# Dashboard_rev6.net
KiCad netlist of a schematic drawn in EAGLE
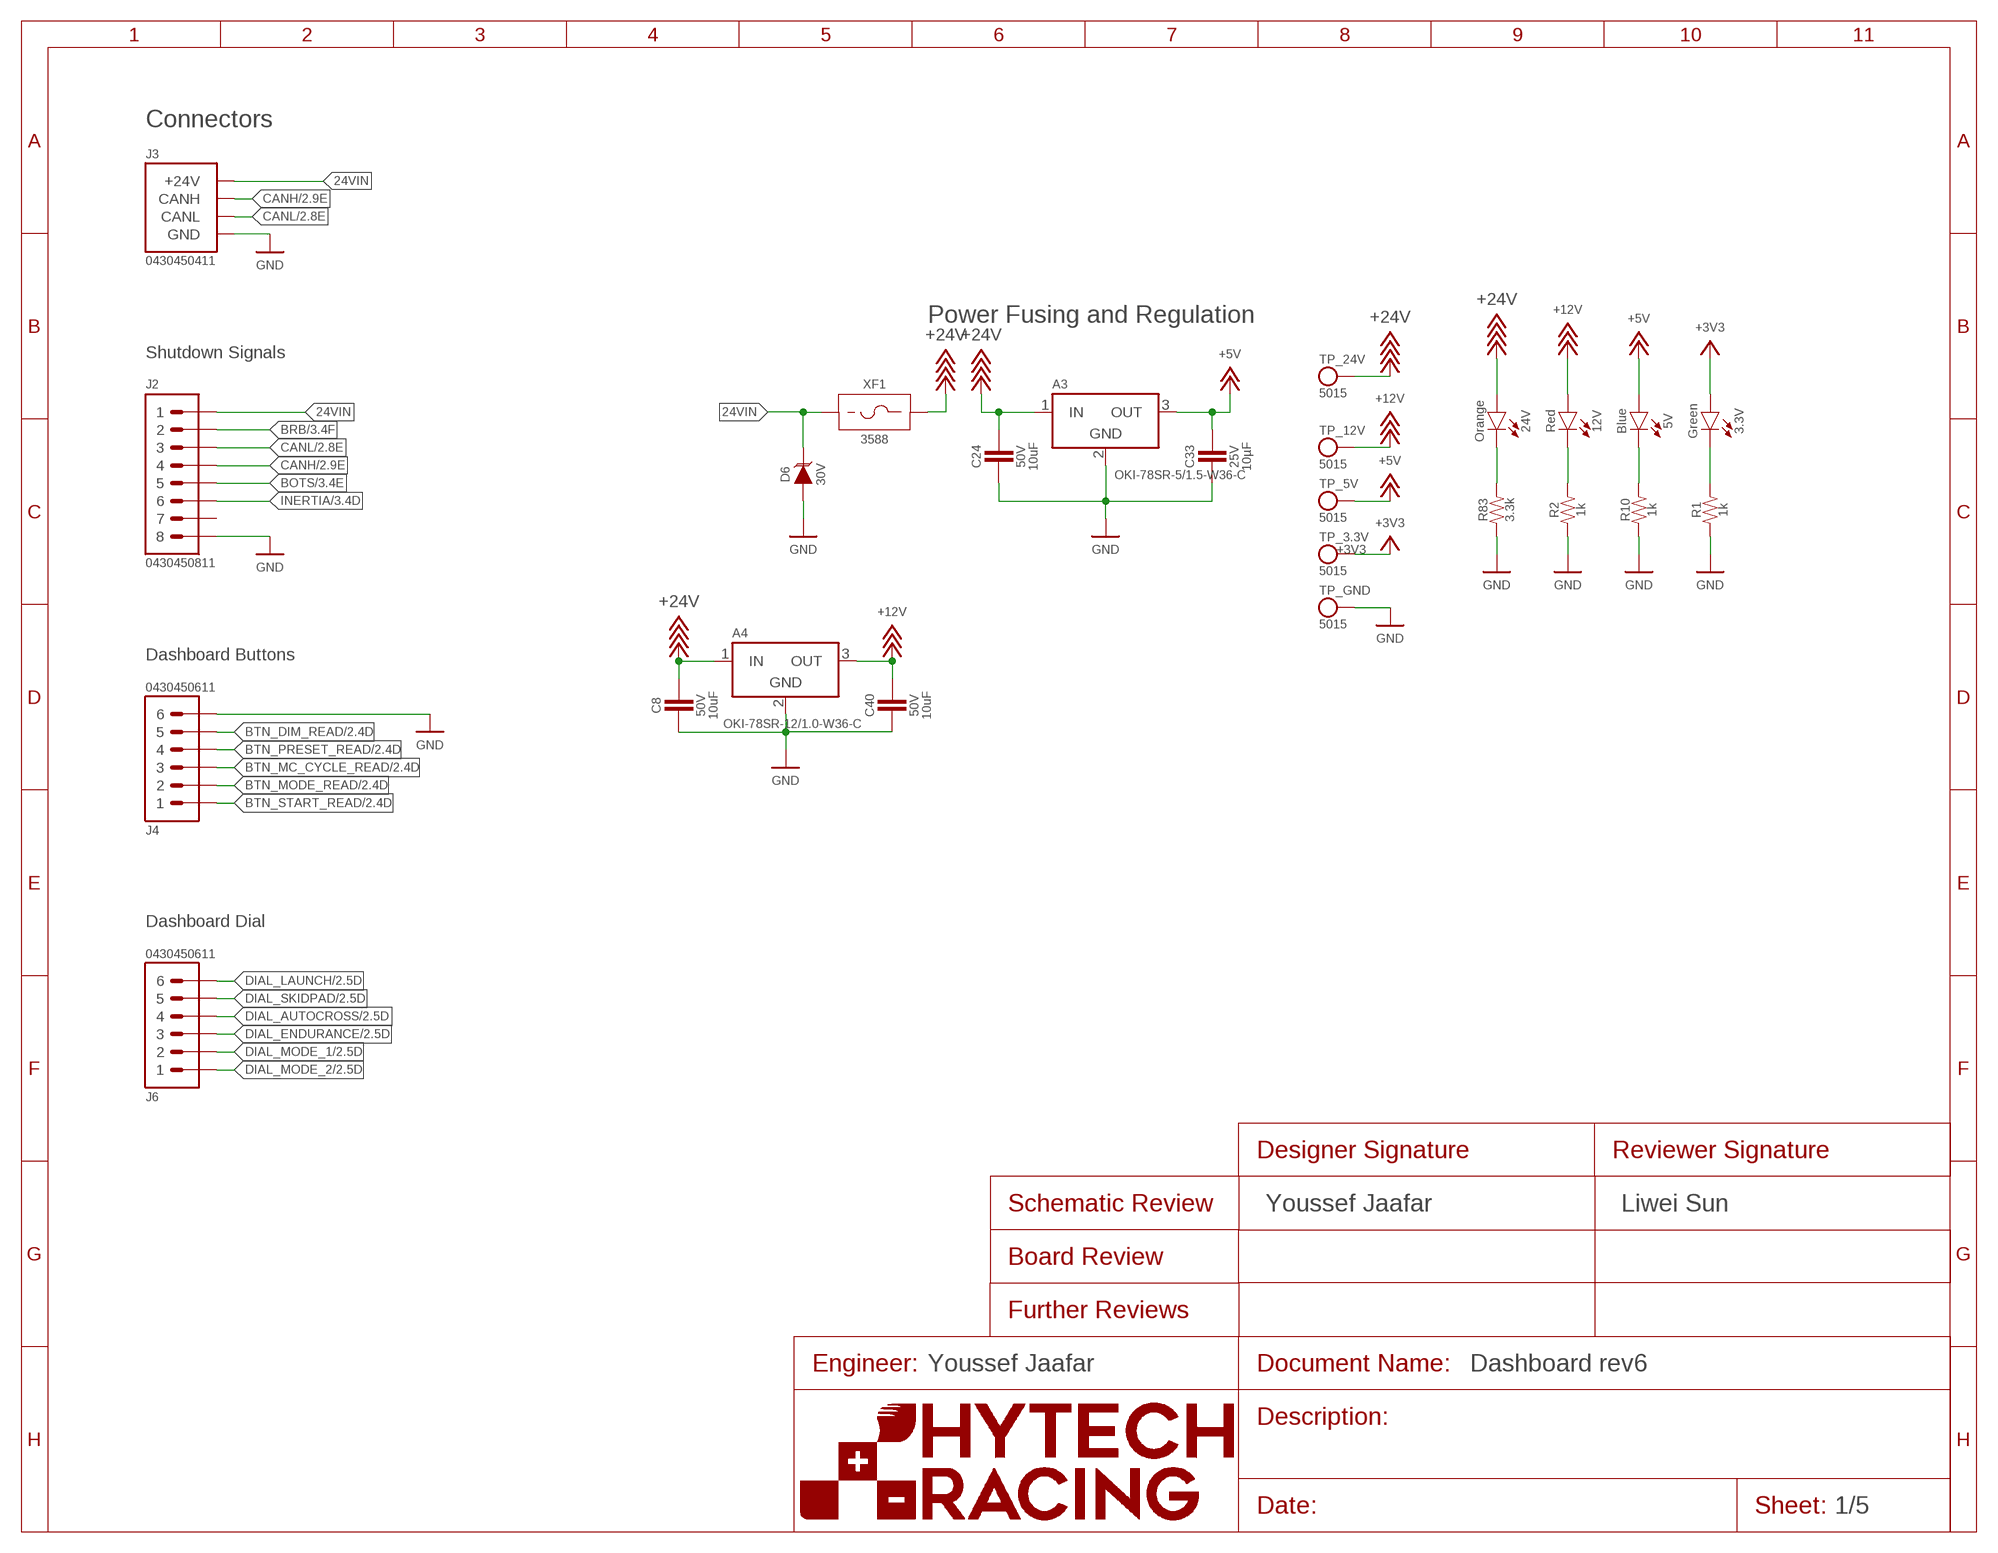
[diagram p0: schematic, sheet 1]
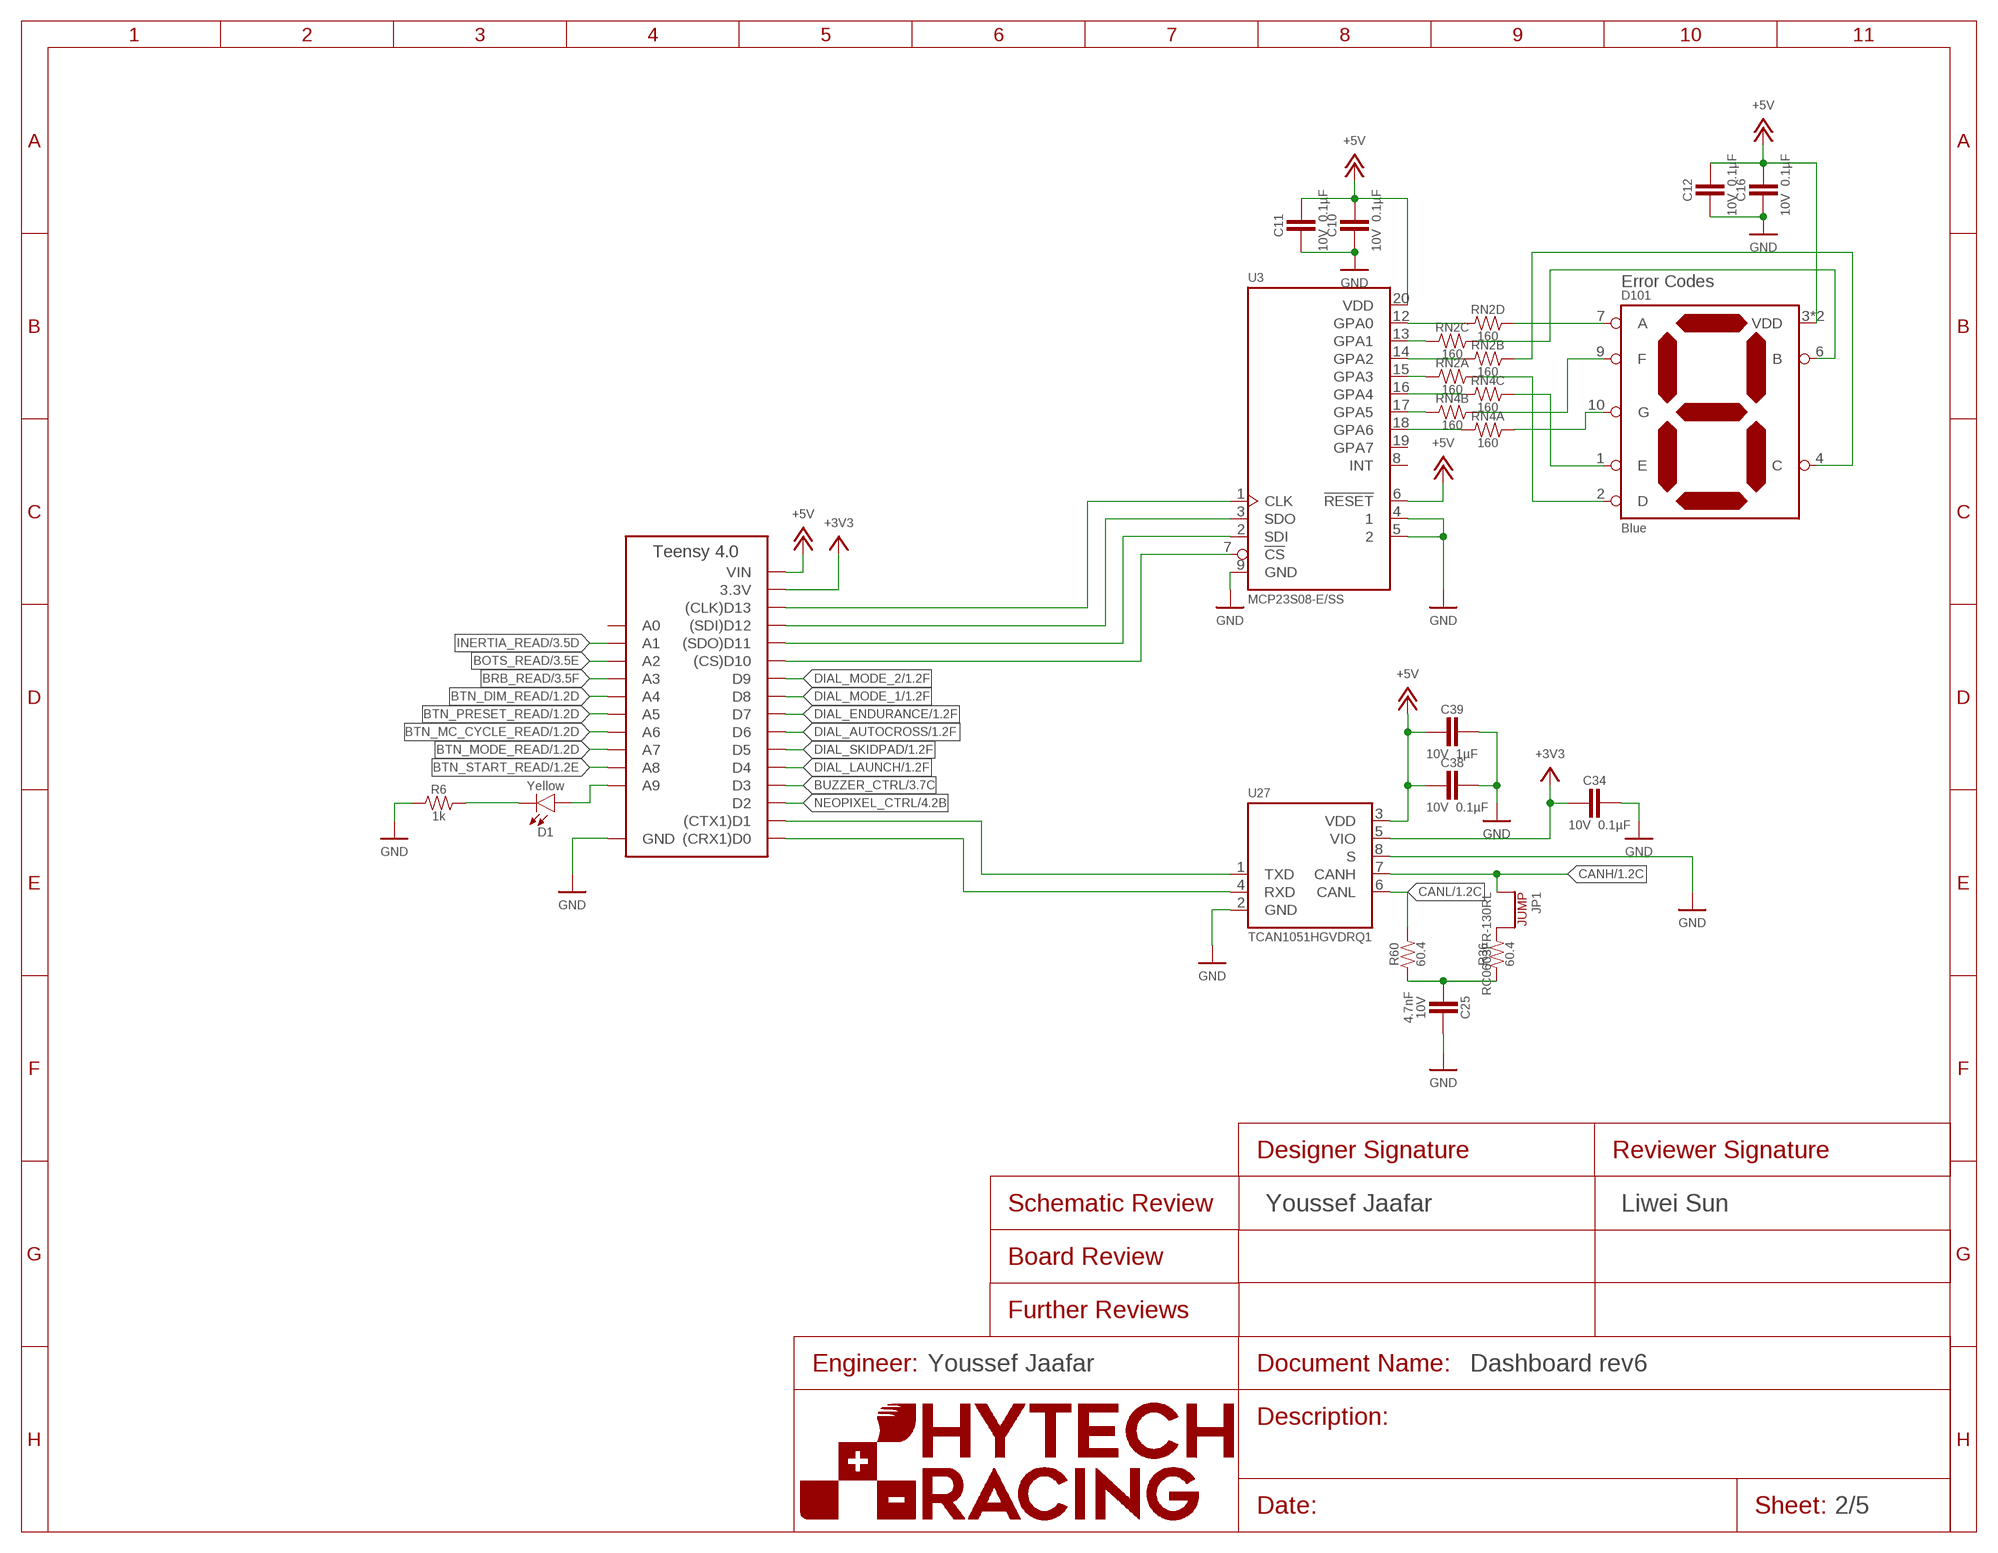
[diagram p1: schematic, sheet 2]
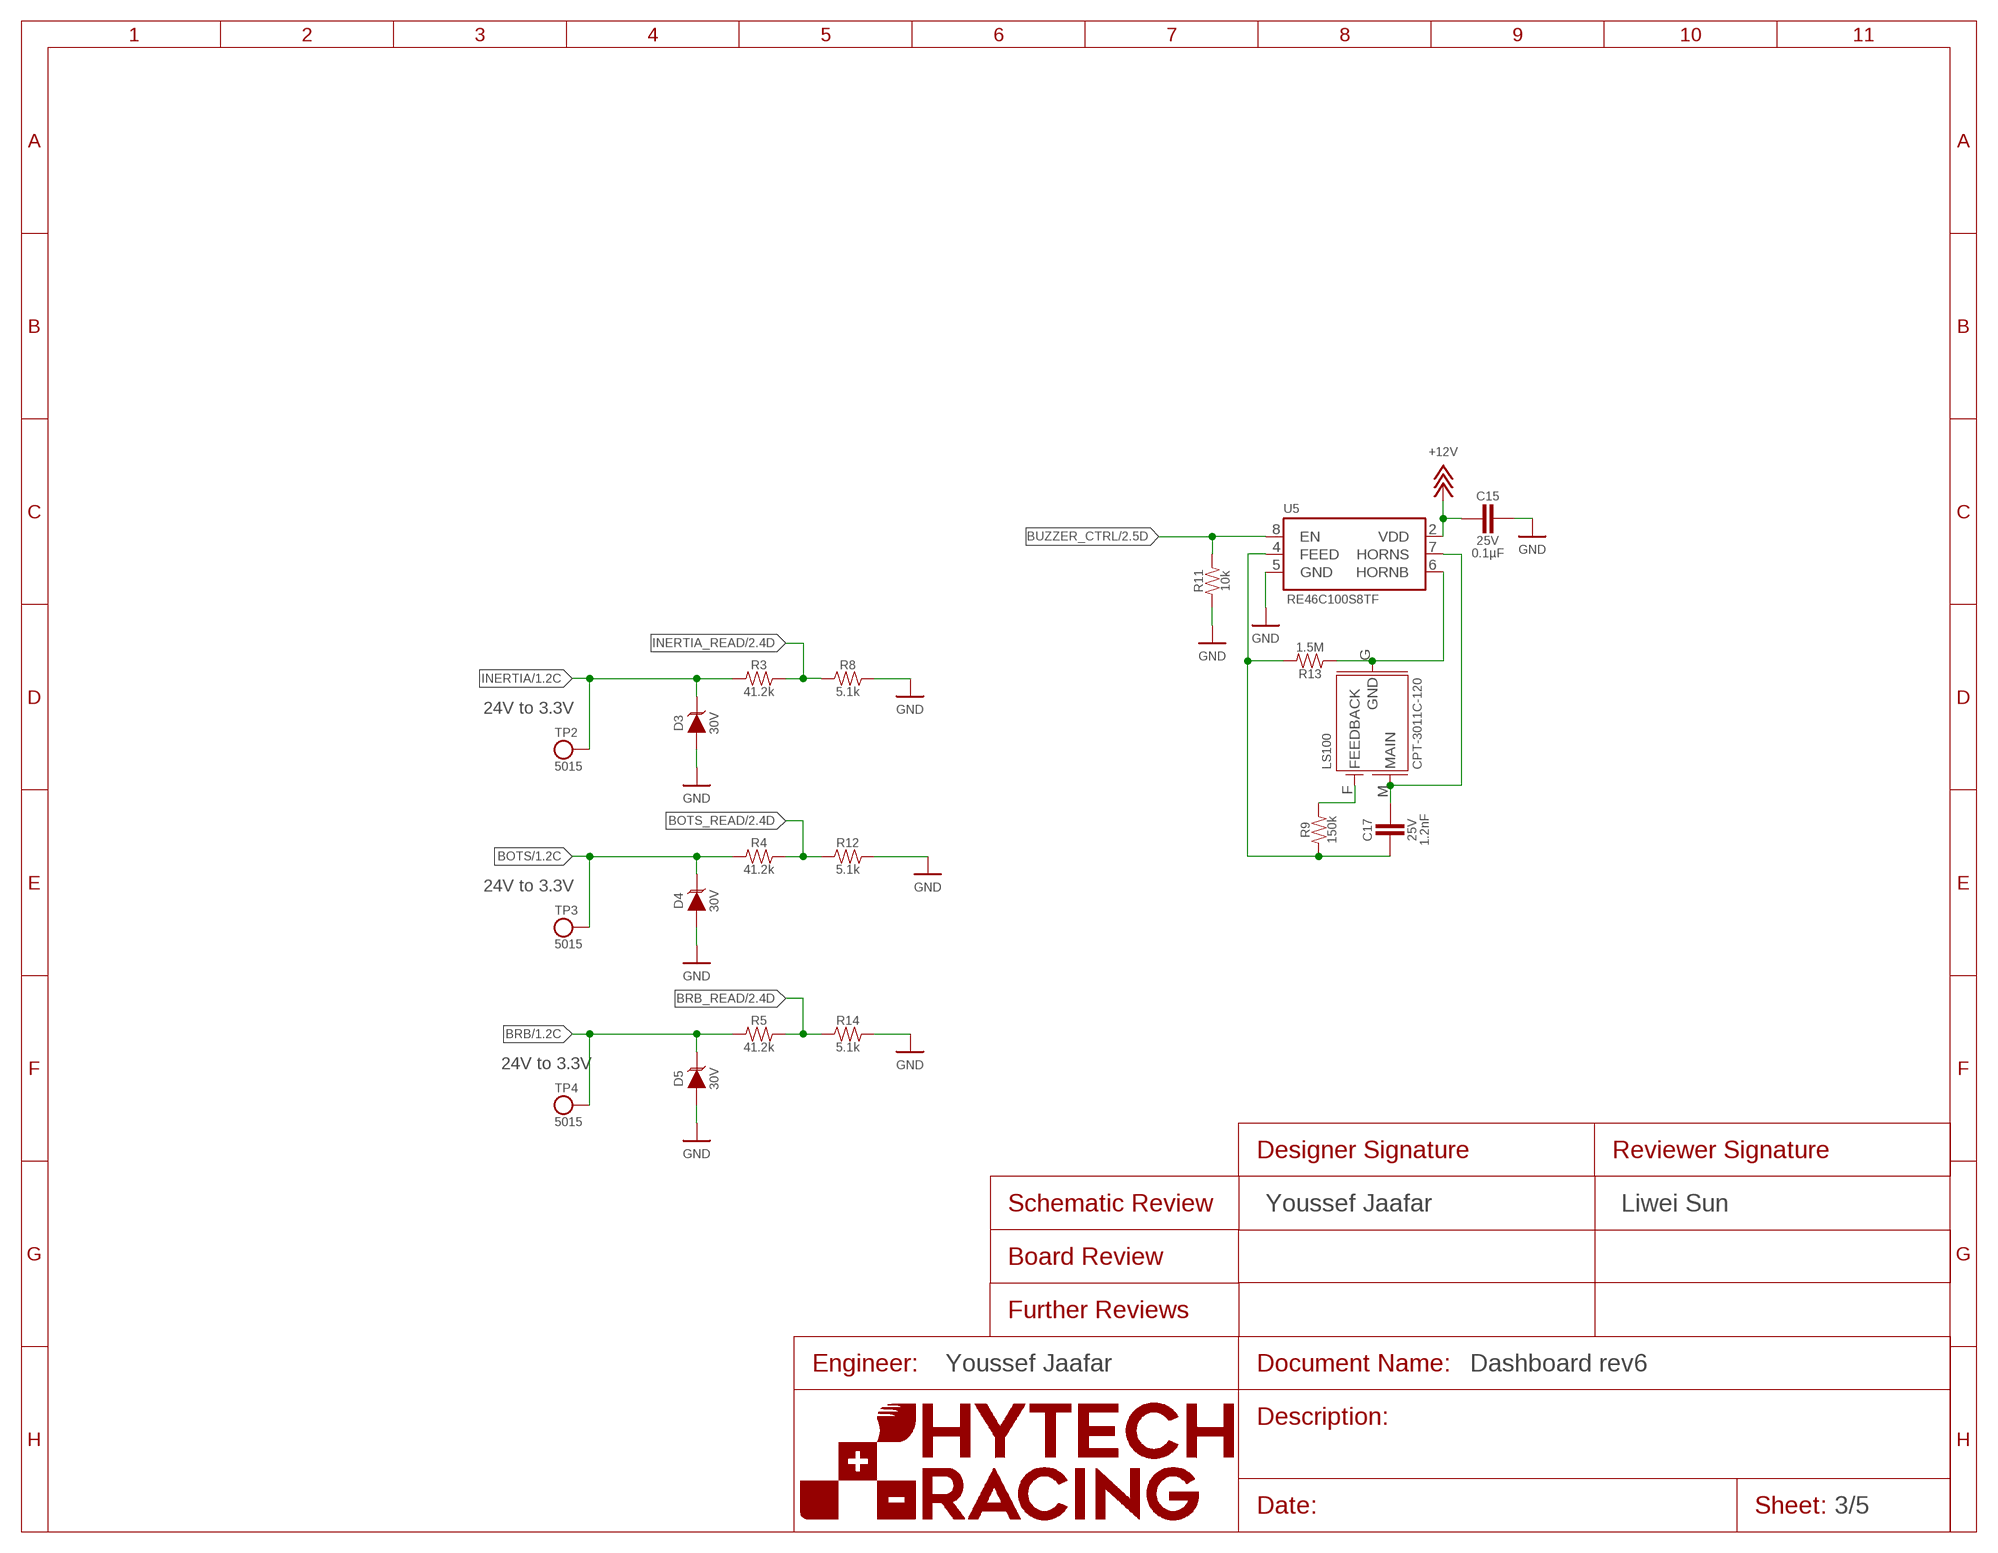
[diagram p2: schematic, sheet 3]
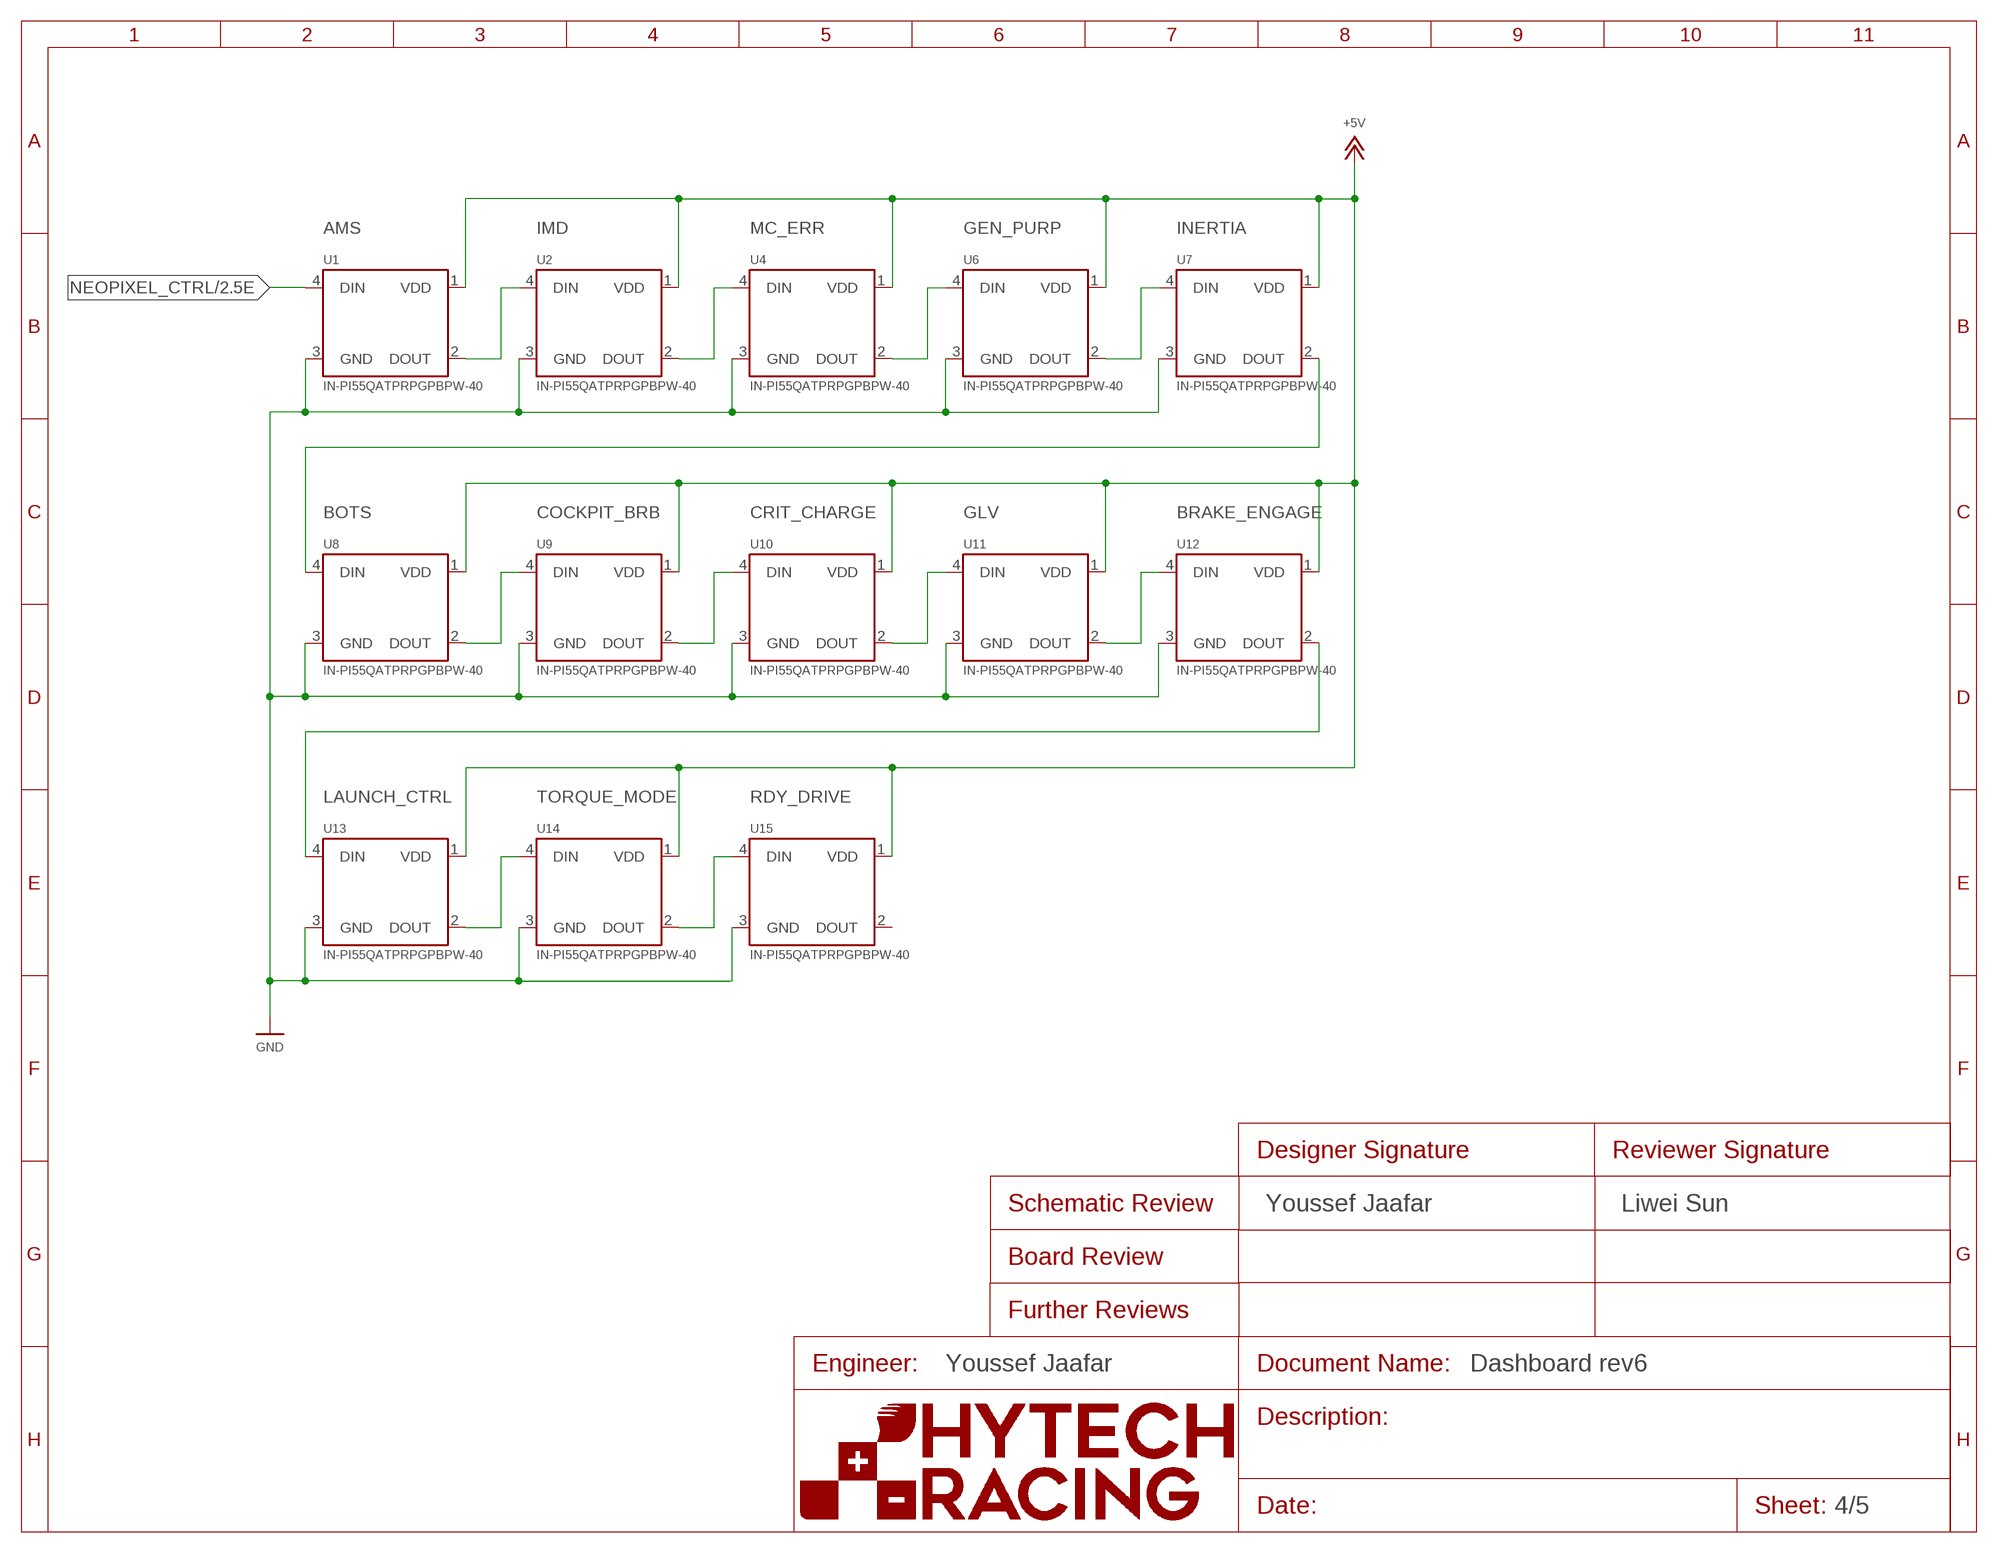
[diagram p3: schematic, sheet 4]
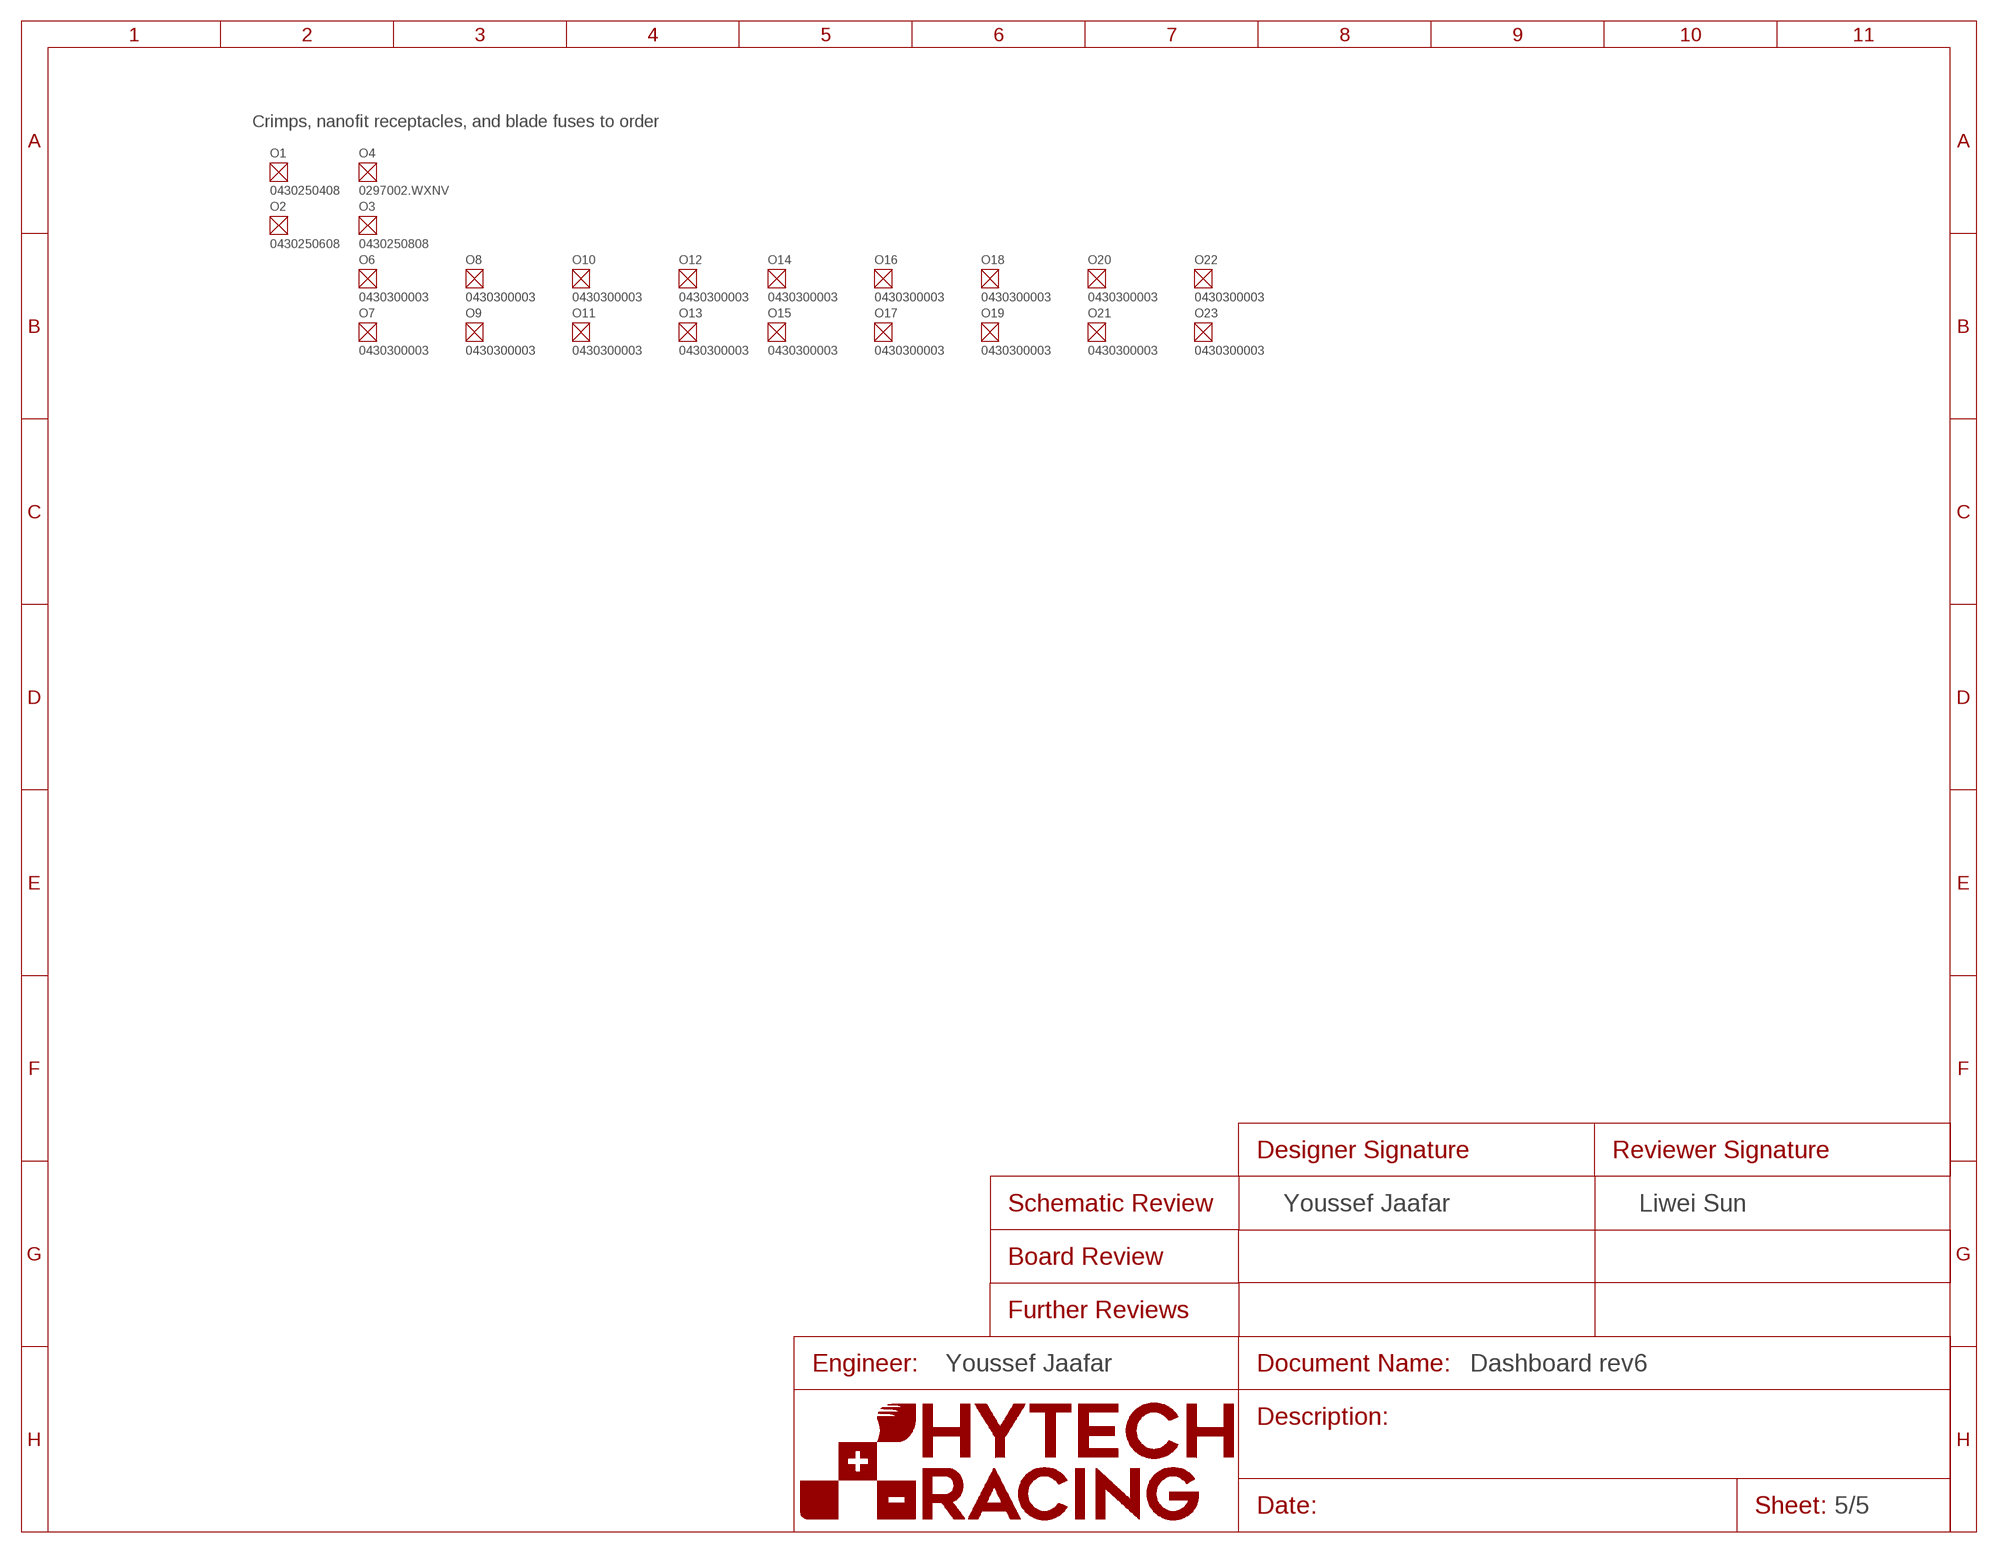
[diagram p4: schematic, sheet 5]

(export (version "E")
  (design (tool "Eeschema 10.0.6"))
  (components
    (comp (ref "U1")
      (value "NEOPIXEL_IN-PI55QATPRPGPBPW-40")
      (footprint "eagle-import:NEOPIXEL")
      (fields (field (name "MPN") "IN-PI55QATPRPGPBPW-40") (field (name "MANUFACTURER") "Inolux"))
      (libsource (lib "eagle-import") (part "NEOPIXEL_IN-PI55QATPRPGPBPW-40"))
    )
    (comp (ref "U2")
      (value "NEOPIXEL_IN-PI55QATPRPGPBPW-40")
      (footprint "eagle-import:NEOPIXEL")
      (fields (field (name "MPN") "IN-PI55QATPRPGPBPW-40") (field (name "MANUFACTURER") "Inolux"))
      (libsource (lib "eagle-import") (part "NEOPIXEL_IN-PI55QATPRPGPBPW-40"))
    )
    (comp (ref "U4")
      (value "NEOPIXEL_IN-PI55QATPRPGPBPW-40")
      (footprint "eagle-import:NEOPIXEL")
      (fields (field (name "MPN") "IN-PI55QATPRPGPBPW-40") (field (name "MANUFACTURER") "Inolux"))
      (libsource (lib "eagle-import") (part "NEOPIXEL_IN-PI55QATPRPGPBPW-40"))
    )
    (comp (ref "U6")
      (value "NEOPIXEL_IN-PI55QATPRPGPBPW-40")
      (footprint "eagle-import:NEOPIXEL")
      (fields (field (name "MPN") "IN-PI55QATPRPGPBPW-40") (field (name "MANUFACTURER") "Inolux"))
      (libsource (lib "eagle-import") (part "NEOPIXEL_IN-PI55QATPRPGPBPW-40"))
    )
    (comp (ref "U7")
      (value "NEOPIXEL_IN-PI55QATPRPGPBPW-40")
      (footprint "eagle-import:NEOPIXEL")
      (fields (field (name "MPN") "IN-PI55QATPRPGPBPW-40") (field (name "MANUFACTURER") "Inolux"))
      (libsource (lib "eagle-import") (part "NEOPIXEL_IN-PI55QATPRPGPBPW-40"))
    )
    (comp (ref "U8")
      (value "NEOPIXEL_IN-PI55QATPRPGPBPW-40")
      (footprint "eagle-import:NEOPIXEL")
      (fields (field (name "MPN") "IN-PI55QATPRPGPBPW-40") (field (name "MANUFACTURER") "Inolux"))
      (libsource (lib "eagle-import") (part "NEOPIXEL_IN-PI55QATPRPGPBPW-40"))
    )
    (comp (ref "U9")
      (value "NEOPIXEL_IN-PI55QATPRPGPBPW-40")
      (footprint "eagle-import:NEOPIXEL")
      (fields (field (name "MPN") "IN-PI55QATPRPGPBPW-40") (field (name "MANUFACTURER") "Inolux"))
      (libsource (lib "eagle-import") (part "NEOPIXEL_IN-PI55QATPRPGPBPW-40"))
    )
    (comp (ref "U10")
      (value "NEOPIXEL_IN-PI55QATPRPGPBPW-40")
      (footprint "eagle-import:NEOPIXEL")
      (fields (field (name "MPN") "IN-PI55QATPRPGPBPW-40") (field (name "MANUFACTURER") "Inolux"))
      (libsource (lib "eagle-import") (part "NEOPIXEL_IN-PI55QATPRPGPBPW-40"))
    )
    (comp (ref "U11")
      (value "NEOPIXEL_IN-PI55QATPRPGPBPW-40")
      (footprint "eagle-import:NEOPIXEL")
      (fields (field (name "MPN") "IN-PI55QATPRPGPBPW-40") (field (name "MANUFACTURER") "Inolux"))
      (libsource (lib "eagle-import") (part "NEOPIXEL_IN-PI55QATPRPGPBPW-40"))
    )
    (comp (ref "U12")
      (value "NEOPIXEL_IN-PI55QATPRPGPBPW-40")
      (footprint "eagle-import:NEOPIXEL")
      (fields (field (name "MPN") "IN-PI55QATPRPGPBPW-40") (field (name "MANUFACTURER") "Inolux"))
      (libsource (lib "eagle-import") (part "NEOPIXEL_IN-PI55QATPRPGPBPW-40"))
    )
    (comp (ref "U13")
      (value "NEOPIXEL_IN-PI55QATPRPGPBPW-40")
      (footprint "eagle-import:NEOPIXEL")
      (fields (field (name "MPN") "IN-PI55QATPRPGPBPW-40") (field (name "MANUFACTURER") "Inolux"))
      (libsource (lib "eagle-import") (part "NEOPIXEL_IN-PI55QATPRPGPBPW-40"))
    )
    (comp (ref "U14")
      (value "NEOPIXEL_IN-PI55QATPRPGPBPW-40")
      (footprint "eagle-import:NEOPIXEL")
      (fields (field (name "MPN") "IN-PI55QATPRPGPBPW-40") (field (name "MANUFACTURER") "Inolux"))
      (libsource (lib "eagle-import") (part "NEOPIXEL_IN-PI55QATPRPGPBPW-40"))
    )
    (comp (ref "U15")
      (value "NEOPIXEL_IN-PI55QATPRPGPBPW-40")
      (footprint "eagle-import:NEOPIXEL")
      (fields (field (name "MPN") "IN-PI55QATPRPGPBPW-40") (field (name "MANUFACTURER") "Inolux"))
      (libsource (lib "eagle-import") (part "NEOPIXEL_IN-PI55QATPRPGPBPW-40"))
    )
    (comp (ref "C15")
      (value "CAPACITOR_0603_25V_0.1UF")
      (footprint "eagle-import:0603-CAP")
      (fields
        (field (name "CAPACITANCE") "0.1µF")
        (field (name "MANUFACTURER") "Samsung Electro-Mechanics")
        (field (name "MPN") "CL10B104KA8NNNC")
        (field (name "TOLERANCE") "10%")
        (field (name "VOLTAGE") "25V")
      )
      (libsource (lib "eagle-import") (part "CAPACITOR_?_060325V_0.1UF"))
    )
    (comp (ref "C17")
      (value "CAPACITOR_0603_25V_1.2NF")
      (footprint "eagle-import:0603-CAP")
      (fields
        (field (name "CAPACITANCE") "1.2nF")
        (field (name "MANUFACTURER") "YAGEO")
        (field (name "MPN") "CC0603KRX7R8BB122")
        (field (name "TOLERANCE") "10%")
        (field (name "VOLTAGE") "25V")
      )
      (libsource (lib "eagle-import") (part "CAPACITOR_?_060325V_1.2NF"))
    )
    (comp (ref "D3")
      (value "TVS_DO-214AA_30V")
      (footprint "eagle-import:DO-214AA")
      (fields
        (field (name "MANUFACTURER") "Bourns Inc.")
        (field (name "MPN") " 1.5SMBJ30A")
        (field (name "VOLTAGE") "30V")
      )
      (libsource (lib "eagle-import") (part "TVS_?_DO-214AA30V"))
    )
    (comp (ref "D4")
      (value "TVS_DO-214AA_30V")
      (footprint "eagle-import:DO-214AA")
      (fields
        (field (name "MANUFACTURER") "Bourns Inc.")
        (field (name "MPN") " 1.5SMBJ30A")
        (field (name "VOLTAGE") "30V")
      )
      (libsource (lib "eagle-import") (part "TVS_?_DO-214AA30V"))
    )
    (comp (ref "D5")
      (value "TVS_DO-214AA_30V")
      (footprint "eagle-import:DO-214AA")
      (fields
        (field (name "MANUFACTURER") "Bourns Inc.")
        (field (name "MPN") " 1.5SMBJ30A")
        (field (name "VOLTAGE") "30V")
      )
      (libsource (lib "eagle-import") (part "TVS_?_DO-214AA30V"))
    )
    (comp (ref "LS100")
      (value "BUZZER_3_PIN_CPT-3011C-120")
      (footprint "eagle-import:CPT-3011C-120")
      (fields
        (field (name "MANUFACTURER") "CUI Devices")
        (field (name "MPN") "CPT-3011C-120")
        (field (name "VOLTAGE") "12V")
      )
      (libsource (lib "eagle-import") (part "BUZZER_3_PIN_CPT-3011C-120"))
    )
    (comp (ref "R3")
      (value "RESISTOR_0603_41.2K")
      (footprint "eagle-import:0603-RES")
      (fields
        (field (name "MANUFACTURER") "Panasonic Electronic Components")
        (field (name "MPN") " ERJ-PB3B4122V")
        (field (name "POWER") "0.2W")
        (field (name "RESISTANCE") "41.2k")
      )
      (libsource (lib "eagle-import") (part "RESISTOR_?_060341.2K"))
    )
    (comp (ref "R4")
      (value "RESISTOR_0603_41.2K")
      (footprint "eagle-import:0603-RES")
      (fields
        (field (name "MANUFACTURER") "Panasonic Electronic Components")
        (field (name "MPN") " ERJ-PB3B4122V")
        (field (name "POWER") "0.2W")
        (field (name "RESISTANCE") "41.2k")
      )
      (libsource (lib "eagle-import") (part "RESISTOR_?_060341.2K"))
    )
    (comp (ref "R5")
      (value "RESISTOR_0603_41.2K")
      (footprint "eagle-import:0603-RES")
      (fields
        (field (name "MANUFACTURER") "Panasonic Electronic Components")
        (field (name "MPN") " ERJ-PB3B4122V")
        (field (name "POWER") "0.2W")
        (field (name "RESISTANCE") "41.2k")
      )
      (libsource (lib "eagle-import") (part "RESISTOR_?_060341.2K"))
    )
    (comp (ref "R8")
      (value "RESISTOR_0603_5.1K")
      (footprint "eagle-import:0603-RES")
      (fields
        (field (name "MANUFACTURER") "Yageo")
        (field (name "MPN") "RC0603FR-075K1L")
        (field (name "POWER") "0.1W")
        (field (name "RESISTANCE") "5.1k")
      )
      (libsource (lib "eagle-import") (part "RESISTOR_?_06035.1K"))
    )
    (comp (ref "R9")
      (value "RESISTOR_0603_150K")
      (footprint "eagle-import:0603-RES")
      (fields
        (field (name "MANUFACTURER") "Panasonic Electronic Components")
        (field (name "MPN") "ERA-3AEB154V")
        (field (name "POWER") "0.1W")
        (field (name "RESISTANCE") "150k")
      )
      (libsource (lib "eagle-import") (part "RESISTOR_?_0603150K"))
    )
    (comp (ref "R11")
      (value "RESISTOR_0603_10K")
      (footprint "eagle-import:0603-RES")
      (fields
        (field (name "MANUFACTURER") "Panasonic Electronic Components")
        (field (name "MPN") "ERA-3ARB103V")
        (field (name "POWER") "0.1W")
        (field (name "RESISTANCE") "10k")
      )
      (libsource (lib "eagle-import") (part "RESISTOR_?_060310K"))
    )
    (comp (ref "R12")
      (value "RESISTOR_0603_5.1K")
      (footprint "eagle-import:0603-RES")
      (fields
        (field (name "MANUFACTURER") "Yageo")
        (field (name "MPN") "RC0603FR-075K1L")
        (field (name "POWER") "0.1W")
        (field (name "RESISTANCE") "5.1k")
      )
      (libsource (lib "eagle-import") (part "RESISTOR_?_06035.1K"))
    )
    (comp (ref "R13")
      (value "RESISTOR_0603_1.5M")
      (footprint "eagle-import:0603-RES")
      (fields
        (field (name "MANUFACTURER") "Yageo")
        (field (name "MPN") "RC0603FR-071M5L")
        (field (name "POWER") "0.1W")
        (field (name "RESISTANCE") "1.5M")
      )
      (libsource (lib "eagle-import") (part "RESISTOR_?_06031.5M"))
    )
    (comp (ref "R14")
      (value "RESISTOR_0603_5.1K")
      (footprint "eagle-import:0603-RES")
      (fields
        (field (name "MANUFACTURER") "Yageo")
        (field (name "MPN") "RC0603FR-075K1L")
        (field (name "POWER") "0.1W")
        (field (name "RESISTANCE") "5.1k")
      )
      (libsource (lib "eagle-import") (part "RESISTOR_?_06035.1K"))
    )
    (comp (ref "TP2")
      (value "TEST_POINT")
      (footprint "eagle-import:5015")
      (fields (field (name "MPN") "5015") (field (name "MANUFACTURER") "Keystone Electronics"))
      (libsource (lib "eagle-import") (part "TEST_POINT"))
    )
    (comp (ref "TP3")
      (value "TEST_POINT")
      (footprint "eagle-import:5015")
      (fields (field (name "MPN") "5015") (field (name "MANUFACTURER") "Keystone Electronics"))
      (libsource (lib "eagle-import") (part "TEST_POINT"))
    )
    (comp (ref "TP4")
      (value "TEST_POINT")
      (footprint "eagle-import:5015")
      (fields (field (name "MPN") "5015") (field (name "MANUFACTURER") "Keystone Electronics"))
      (libsource (lib "eagle-import") (part "TEST_POINT"))
    )
    (comp (ref "U5")
      (value "RE46C100")
      (footprint "eagle-import:SOIC-08(NARROW,0.15_)")
      (fields (field (name "MPN") " RE46C100S8TF") (field (name "MANUFACTURER") "Microchip Technology"))
      (libsource (lib "eagle-import") (part "RE46C100"))
    )
    (comp (ref "3.3V")
      (value "LED_0603_GREEN")
      (footprint "eagle-import:0603-LED")
      (fields
        (field (name "COLOR") "Green")
        (field (name "MANUFACTURER") "Kingbright")
        (field (name "MPN") "APT1608ZGCK")
      )
      (libsource (lib "eagle-import") (part "HyTechDevices - Copy_LED_?_0603GREEN"))
    )
    (comp (ref "5V")
      (value "LED_0603_BLUE")
      (footprint "eagle-import:0603-LED")
      (fields
        (field (name "COLOR") "Blue")
        (field (name "MANUFACTURER") "Kingbright")
        (field (name "MPN") "APT1608VBC/D")
      )
      (libsource (lib "eagle-import") (part "HyTechDevices - Copy_LED_?_0603BLUE"))
    )
    (comp (ref "12V")
      (value "LED_0603_RED")
      (footprint "eagle-import:0603-LED")
      (fields
        (field (name "COLOR") "Red")
        (field (name "MANUFACTURER") "Kingbright")
        (field (name "MPN") "APT1608SECK/J3-PRV")
      )
      (libsource (lib "eagle-import") (part "HyTechDevices - Copy_LED_?_0603RED"))
    )
    (comp (ref "24V")
      (value "LED_0603_ORANGE")
      (footprint "eagle-import:0603-LED")
      (fields
        (field (name "COLOR") "Orange")
        (field (name "MANUFACTURER") "Kingbright")
        (field (name "MPN") "APT1608SECK")
      )
      (libsource (lib "eagle-import") (part "LED_?_0603ORANGE"))
    )
    (comp (ref "A3")
      (value "VOLTAGE_REGULATOR_MODULE_OKI-78SR_5V")
      (footprint "eagle-import:OKI-78SR")
      (fields
        (field (name "MANUFACTURER") "Murata Power Solutions Inc.")
        (field (name "MPN") "OKI-78SR-5/1.5-W36-C")
      )
      (libsource (lib "eagle-import") (part "VOLTAGE_REGULATOR_MODULE_?_OKI-78SR5V"))
    )
    (comp (ref "A4")
      (value "VOLTAGE_REGULATOR_MODULE_OKI-78SR_12V")
      (footprint "eagle-import:OKI-78SR")
      (fields
        (field (name "MANUFACTURER") "Murata Power Solutions Inc.")
        (field (name "MPN") "OKI-78SR-12/1.0-W36-C")
      )
      (libsource (lib "eagle-import") (part "VOLTAGE_REGULATOR_MODULE_?_OKI-78SR12V"))
    )
    (comp (ref "C8")
      (value "CAPACITOR_0805_50V_10UF")
      (footprint "eagle-import:0805-CAP")
      (fields
        (field (name "CAPACITANCE") "10uF")
        (field (name "MANUFACTURER") "Murata")
        (field (name "MPN") " GRM21BR61H106KE43L")
        (field (name "TOLERANCE") "10%")
        (field (name "VOLTAGE") "50V")
      )
      (libsource (lib "eagle-import") (part "CAPACITOR_?_080550V_10UF"))
    )
    (comp (ref "C24")
      (value "CAPACITOR_0805_50V_10UF")
      (footprint "eagle-import:0805-CAP")
      (fields
        (field (name "CAPACITANCE") "10uF")
        (field (name "MANUFACTURER") "Murata")
        (field (name "MPN") " GRM21BR61H106KE43L")
        (field (name "TOLERANCE") "10%")
        (field (name "VOLTAGE") "50V")
      )
      (libsource (lib "eagle-import") (part "CAPACITOR_?_080550V_10UF"))
    )
    (comp (ref "C33")
      (value "CAPACITOR_0603_25V_10UF")
      (footprint "eagle-import:0603-CAP")
      (fields
        (field (name "CAPACITANCE") "10µF")
        (field (name "MANUFACTURER") "Murata Electronics")
        (field (name "MPN") "GRM188R61E106MA73D")
        (field (name "TOLERANCE") "20%")
        (field (name "VOLTAGE") "25V")
      )
      (libsource (lib "eagle-import") (part "CAPACITOR_?_060325V_10UF"))
    )
    (comp (ref "C40")
      (value "CAPACITOR_0805_50V_10UF")
      (footprint "eagle-import:0805-CAP")
      (fields
        (field (name "CAPACITANCE") "10uF")
        (field (name "MANUFACTURER") "Murata")
        (field (name "MPN") " GRM21BR61H106KE43L")
        (field (name "TOLERANCE") "10%")
        (field (name "VOLTAGE") "50V")
      )
      (libsource (lib "eagle-import") (part "CAPACITOR_?_080550V_10UF"))
    )
    (comp (ref "D6")
      (value "TVS_DO-214AA_30V")
      (footprint "eagle-import:DO-214AA")
      (fields
        (field (name "MANUFACTURER") "Bourns Inc.")
        (field (name "MPN") " 1.5SMBJ30A")
        (field (name "VOLTAGE") "30V")
      )
      (libsource (lib "eagle-import") (part "TVS_?_DO-214AA30V"))
    )
    (comp (ref "J2")
      (value "CONNECTOR-8_μF_S_RA_")
      (footprint "eagle-import:MOLEX_MICROFIT_SMD_RIGHTANGLE_08_DUAL")
      (fields (field (name "MPN") "0430450811") (field (name "MANUFACTURER") "Molex"))
      (libsource (lib "eagle-import") (part "CONNECTOR-8_?_μF_S_RA"))
    )
    (comp (ref "J3")
      (value "CONNECTOR-CAN_μF_S_RA_")
      (footprint "eagle-import:MOLEX_MICROFIT_SMD_RIGHTANGLE_04_DUAL")
      (fields (field (name "MPN") "0430450411") (field (name "MANUFACTURER") "Molex"))
      (libsource (lib "eagle-import") (part "CONNECTOR-CAN_?_μF_S_RA"))
    )
    (comp (ref "J4")
      (value "CONNECTOR-6_μF_S_RA_")
      (footprint "eagle-import:MOLEX_MICROFIT_SMD_RIGHTANGLE_06_DUAL")
      (fields (field (name "MPN") "0430450611") (field (name "MANUFACTURER") "Molex"))
      (libsource (lib "eagle-import") (part "CONNECTOR-6_?_μF_S_RA"))
    )
    (comp (ref "J6")
      (value "CONNECTOR-6_μF_S_RA_")
      (footprint "eagle-import:MOLEX_MICROFIT_SMD_RIGHTANGLE_06_DUAL")
      (fields (field (name "MPN") "0430450611") (field (name "MANUFACTURER") "Molex"))
      (libsource (lib "eagle-import") (part "CONNECTOR-6_?_μF_S_RA"))
    )
    (comp (ref "R1")
      (value "RESISTOR_0603_1K")
      (footprint "eagle-import:0603-RES")
      (fields
        (field (name "MANUFACTURER") "TE Connectivity Passive Product")
        (field (name "MPN") " CPF-A-0603B1K0E")
        (field (name "POWER") "0.0625W")
        (field (name "RESISTANCE") "1k")
      )
      (libsource (lib "eagle-import") (part "RESISTOR_?_06031K"))
    )
    (comp (ref "R2")
      (value "RESISTOR_0603_1K")
      (footprint "eagle-import:0603-RES")
      (fields
        (field (name "MANUFACTURER") "TE Connectivity Passive Product")
        (field (name "MPN") " CPF-A-0603B1K0E")
        (field (name "POWER") "0.0625W")
        (field (name "RESISTANCE") "1k")
      )
      (libsource (lib "eagle-import") (part "RESISTOR_?_06031K"))
    )
    (comp (ref "R10")
      (value "RESISTOR_0603_1K")
      (footprint "eagle-import:0603-RES")
      (fields
        (field (name "MANUFACTURER") "TE Connectivity Passive Product")
        (field (name "MPN") " CPF-A-0603B1K0E")
        (field (name "POWER") "0.0625W")
        (field (name "RESISTANCE") "1k")
      )
      (libsource (lib "eagle-import") (part "RESISTOR_?_06031K"))
    )
    (comp (ref "R83")
      (value "RESISTOR_0603_3.3K")
      (footprint "eagle-import:0603-RES")
      (fields
        (field (name "MANUFACTURER") "Panasonic Electronic Components")
        (field (name "MPN") "ERJ-PB3D3301V")
        (field (name "POWER") "0.2W")
        (field (name "RESISTANCE") "3.3k")
      )
      (libsource (lib "eagle-import") (part "RESISTOR_?_06033.3K"))
    )
    (comp (ref "TP_3.3V")
      (value "TEST_POINT")
      (footprint "eagle-import:5015")
      (fields
        (field (name "MPN") "5015")
        (field (name "MANUFACTURER") "Keystone Electronics")
        (field (name "SIGNAL") "+3V3")
      )
      (libsource (lib "eagle-import") (part "TEST_POINT"))
    )
    (comp (ref "TP_5V")
      (value "TEST_POINT")
      (footprint "eagle-import:5015")
      (fields (field (name "MPN") "5015") (field (name "MANUFACTURER") "Keystone Electronics"))
      (libsource (lib "eagle-import") (part "TEST_POINT"))
    )
    (comp (ref "TP_12V")
      (value "TEST_POINT")
      (footprint "eagle-import:5015")
      (fields (field (name "MPN") "5015") (field (name "MANUFACTURER") "Keystone Electronics"))
      (libsource (lib "eagle-import") (part "TEST_POINT"))
    )
    (comp (ref "TP_24V")
      (value "TEST_POINT")
      (footprint "eagle-import:5015")
      (fields (field (name "MPN") "5015") (field (name "MANUFACTURER") "Keystone Electronics"))
      (libsource (lib "eagle-import") (part "TEST_POINT"))
    )
    (comp (ref "TP_GND")
      (value "TEST_POINT")
      (footprint "eagle-import:5015")
      (fields (field (name "MPN") "5015") (field (name "MANUFACTURER") "Keystone Electronics"))
      (libsource (lib "eagle-import") (part "TEST_POINT"))
    )
    (comp (ref "XF1")
      (value "FUSE_HOLDER_MINIBLADESMD")
      (footprint "eagle-import:3588")
      (fields (field (name "MANUFACTURER") "Keystone Electronics") (field (name "MPN") "3588"))
      (libsource (lib "eagle-import") (part "FUSE_HOLDER_SMDMINIBLADE"))
    )
    (comp (ref "A2")
      (value "TEENSY_4.0SM")
      (footprint "eagle-import:TEENSY_SHORT_SSM")
      (libsource (lib "eagle-import") (part "TEENSY_4.0SM"))
    )
    (comp (ref "C10")
      (value "CAPACITOR_0603_10V_0.1UF")
      (footprint "eagle-import:0603-CAP")
      (fields
        (field (name "CAPACITANCE") "0.1µF")
        (field (name "MANUFACTURER") "Vishay Vitramon")
        (field (name "MPN") "VJ0603Y104JXQPW1BC")
        (field (name "TOLERANCE") "5%")
        (field (name "VOLTAGE") "10V")
      )
      (libsource (lib "eagle-import") (part "CAPACITOR_?_060310V_0.1UF"))
    )
    (comp (ref "C11")
      (value "CAPACITOR_0603_10V_0.1UF")
      (footprint "eagle-import:0603-CAP")
      (fields
        (field (name "CAPACITANCE") "0.1µF")
        (field (name "MANUFACTURER") "Vishay Vitramon")
        (field (name "MPN") "VJ0603Y104JXQPW1BC")
        (field (name "TOLERANCE") "5%")
        (field (name "VOLTAGE") "10V")
      )
      (libsource (lib "eagle-import") (part "CAPACITOR_?_060310V_0.1UF"))
    )
    (comp (ref "C12")
      (value "CAPACITOR_0603_10V_0.1UF")
      (footprint "eagle-import:0603-CAP")
      (fields
        (field (name "CAPACITANCE") "0.1µF")
        (field (name "MANUFACTURER") "Vishay Vitramon")
        (field (name "MPN") "VJ0603Y104JXQPW1BC")
        (field (name "TOLERANCE") "5%")
        (field (name "VOLTAGE") "10V")
      )
      (libsource (lib "eagle-import") (part "CAPACITOR_?_060310V_0.1UF"))
    )
    (comp (ref "C16")
      (value "CAPACITOR_0603_10V_0.1UF")
      (footprint "eagle-import:0603-CAP")
      (fields
        (field (name "CAPACITANCE") "0.1µF")
        (field (name "MANUFACTURER") "Vishay Vitramon")
        (field (name "MPN") "VJ0603Y104JXQPW1BC")
        (field (name "TOLERANCE") "5%")
        (field (name "VOLTAGE") "10V")
      )
      (libsource (lib "eagle-import") (part "CAPACITOR_?_060310V_0.1UF"))
    )
    (comp (ref "C25")
      (value "CAPACITOR_0603_10V_4.7NF")
      (footprint "eagle-import:0603-CAP")
      (fields
        (field (name "CAPACITANCE") "4.7nF")
        (field (name "MANUFACTURER") "Würth Elektronik")
        (field (name "MPN") "885012206012")
        (field (name "TOLERANCE") "10%")
        (field (name "VOLTAGE") "10V")
      )
      (libsource (lib "eagle-import") (part "CAPACITOR_?_060310V_4.7NF"))
    )
    (comp (ref "C34")
      (value "CAPACITOR_0603_10V_0.1UF")
      (footprint "eagle-import:0603-CAP")
      (fields
        (field (name "CAPACITANCE") "0.1µF")
        (field (name "MANUFACTURER") "Vishay Vitramon")
        (field (name "MPN") "VJ0603Y104JXQPW1BC")
        (field (name "TOLERANCE") "5%")
        (field (name "VOLTAGE") "10V")
      )
      (libsource (lib "eagle-import") (part "CAPACITOR_?_060310V_0.1UF"))
    )
    (comp (ref "C38")
      (value "CAPACITOR_0603_10V_0.1UF")
      (footprint "eagle-import:0603-CAP")
      (fields
        (field (name "CAPACITANCE") "0.1µF")
        (field (name "MANUFACTURER") "Vishay Vitramon")
        (field (name "MPN") "VJ0603Y104JXQPW1BC")
        (field (name "TOLERANCE") "5%")
        (field (name "VOLTAGE") "10V")
      )
      (libsource (lib "eagle-import") (part "CAPACITOR_?_060310V_0.1UF"))
    )
    (comp (ref "C39")
      (value "CAPACITOR_0603_10V_1UF")
      (footprint "eagle-import:0603-CAP")
      (fields
        (field (name "CAPACITANCE") "1µF")
        (field (name "MANUFACTURER") "Yageo")
        (field (name "MPN") "CC0603KRX7R6BB105")
        (field (name "TOLERANCE") "10%")
        (field (name "VOLTAGE") "10V")
      )
      (libsource (lib "eagle-import") (part "CAPACITOR_?_060310V_1UF"))
    )
    (comp (ref "D1")
      (value "LED_0603_YELLOW")
      (footprint "eagle-import:0603-LED")
      (fields
        (field (name "COLOR") "Yellow")
        (field (name "MANUFACTURER") "Kingbright")
        (field (name "MPN") "APT1608SYCK/J3-PRV")
      )
      (libsource (lib "eagle-import") (part "LED_?_0603YELLOW"))
    )
    (comp (ref "D101")
      (value "LED_7_SEGMENT_BLUE_DSM7TA")
      (footprint "eagle-import:DSM7T")
      (fields
        (field (name "COLOR") "Blue")
        (field (name "MANUFACTURER") "Visual Communications Company")
        (field (name "MPN") "DSM7TA56106T")
      )
      (libsource (lib "eagle-import") (part "LED_7_SEGMENT_DSM7TABLUE_"))
    )
    (comp (ref "JP1")
      (value "JUMPER_0603_")
      (footprint "eagle-import:0603-RES")
      (fields (field (name "MPN") "RC0603FR-130RL") (field (name "MANUFACTURER") "YAGEO"))
      (libsource (lib "eagle-import") (part "JUMPER_?_0603"))
    )
    (comp (ref "R6")
      (value "RESISTOR_0603_1K")
      (footprint "eagle-import:0603-RES")
      (fields
        (field (name "MANUFACTURER") "TE Connectivity Passive Product")
        (field (name "MPN") " CPF-A-0603B1K0E")
        (field (name "POWER") "0.0625W")
        (field (name "RESISTANCE") "1k")
      )
      (libsource (lib "eagle-import") (part "RESISTOR_?_06031K"))
    )
    (comp (ref "R36")
      (value "RESISTOR_0603_60.4")
      (footprint "eagle-import:0603-RES")
      (fields
        (field (name "MANUFACTURER") "Yageo")
        (field (name "MPN") "RC0603FR-0760R4L")
        (field (name "POWER") "0.1W")
        (field (name "RESISTANCE") "60.4")
      )
      (libsource (lib "eagle-import") (part "RESISTOR_?_060360.4"))
    )
    (comp (ref "R60")
      (value "RESISTOR_0603_60.4")
      (footprint "eagle-import:0603-RES")
      (fields
        (field (name "MANUFACTURER") "Yageo")
        (field (name "MPN") "RC0603FR-0760R4L")
        (field (name "POWER") "0.1W")
        (field (name "RESISTANCE") "60.4")
      )
      (libsource (lib "eagle-import") (part "RESISTOR_?_060360.4"))
    )
    (comp (ref "RN2")
      (value "RESISTOR_NETWORK_4_160")
      (footprint "eagle-import:1206-RES-ARRAY")
      (fields
        (field (name "MANUFACTURER") "Yageo")
        (field (name "MPN") "YC164-JR-07160RL")
        (field (name "POWER") "1/16W")
        (field (name "RESISTANCE") "160")
      )
      (libsource (lib "eagle-import") (part "RESISTOR_NETWORK_4_160"))
    )
    (comp (ref "RN4")
      (value "RESISTOR_NETWORK_4_160")
      (footprint "eagle-import:1206-RES-ARRAY")
      (fields
        (field (name "MANUFACTURER") "Yageo")
        (field (name "MPN") "YC164-JR-07160RL")
        (field (name "POWER") "1/16W")
        (field (name "RESISTANCE") "160")
      )
      (libsource (lib "eagle-import") (part "RESISTOR_NETWORK_4_160"))
    )
    (comp (ref "U3")
      (value "MCP23S08")
      (footprint "eagle-import:SSOP-20")
      (fields (field (name "MPN") "MCP23S08-E/SS") (field (name "MANUFACTURER") "Microchip Technology"))
      (libsource (lib "eagle-import") (part "MCP23S08"))
    )
    (comp (ref "U27")
      (value "TCAN1051HQV-Q1")
      (footprint "eagle-import:SOIC-08(NARROW,0.15_)")
      (fields (field (name "MANUFACTURER") "Texas Instruments") (field (name "MPN") "TCAN1051HGVDRQ1"))
      (libsource (lib "eagle-import") (part "TCAN1051V-Q1HQ"))
    )
  )
  (nets
    (net (code "1") (name "+3V3") (class "Default")
      (node (ref "3.3V") (pin "2") (pinfunction "A_2") (pintype "passive"))
      (node (ref "A2") (pin "3.3V") (pinfunction "3.3V_3.3V") (pintype "power_in"))
      (node (ref "C34") (pin "2") (pinfunction "2_2") (pintype "passive"))
      (node (ref "TP_3.3V") (pin "1") (pinfunction "1_1") (pintype "passive"))
      (node (ref "U27") (pin "5") (pinfunction "VIO_5") (pintype "power_in"))
    )
    (net (code "2") (name "+5V") (class "Default")
      (node (ref "5V") (pin "2") (pinfunction "A_2") (pintype "passive"))
      (node (ref "A2") (pin "VIN") (pinfunction "VIN_VIN") (pintype "power_in"))
      (node (ref "A3") (pin "3") (pinfunction "OUT_3") (pintype "power_in"))
      (node (ref "C10") (pin "1") (pinfunction "1_1") (pintype "passive"))
      (node (ref "C11") (pin "1") (pinfunction "1_1") (pintype "passive"))
      (node (ref "C12") (pin "1") (pinfunction "1_1") (pintype "passive"))
      (node (ref "C16") (pin "1") (pinfunction "1_1") (pintype "passive"))
      (node (ref "C33") (pin "1") (pinfunction "1_1") (pintype "passive"))
      (node (ref "C38") (pin "2") (pinfunction "2_2") (pintype "passive"))
      (node (ref "C39") (pin "2") (pinfunction "2_2") (pintype "passive"))
      (node (ref "D101") (pin "3") (pinfunction "VDD_3") (pintype "power_in"))
      (node (ref "D101") (pin "8") (pinfunction "VDD_8") (pintype "power_in"))
      (node (ref "TP_5V") (pin "1") (pinfunction "1_1") (pintype "passive"))
      (node (ref "U1") (pin "1") (pinfunction "VDD_1") (pintype "power_in"))
      (node (ref "U10") (pin "1") (pinfunction "VDD_1") (pintype "power_in"))
      (node (ref "U11") (pin "1") (pinfunction "VDD_1") (pintype "power_in"))
      (node (ref "U12") (pin "1") (pinfunction "VDD_1") (pintype "power_in"))
      (node (ref "U13") (pin "1") (pinfunction "VDD_1") (pintype "power_in"))
      (node (ref "U14") (pin "1") (pinfunction "VDD_1") (pintype "power_in"))
      (node (ref "U15") (pin "1") (pinfunction "VDD_1") (pintype "power_in"))
      (node (ref "U2") (pin "1") (pinfunction "VDD_1") (pintype "power_in"))
      (node (ref "U27") (pin "3") (pinfunction "VDD_3") (pintype "power_in"))
      (node (ref "U3") (pin "20") (pinfunction "VDD_20") (pintype "power_in"))
      (node (ref "U3") (pin "6") (pinfunction "~{RESET}_6") (pintype "input"))
      (node (ref "U4") (pin "1") (pinfunction "VDD_1") (pintype "power_in"))
      (node (ref "U6") (pin "1") (pinfunction "VDD_1") (pintype "power_in"))
      (node (ref "U7") (pin "1") (pinfunction "VDD_1") (pintype "power_in"))
      (node (ref "U8") (pin "1") (pinfunction "VDD_1") (pintype "power_in"))
      (node (ref "U9") (pin "1") (pinfunction "VDD_1") (pintype "power_in"))
    )
    (net (code "3") (name "+12V") (class "Default")
      (node (ref "12V") (pin "2") (pinfunction "A_2") (pintype "passive"))
      (node (ref "A4") (pin "3") (pinfunction "OUT_3") (pintype "power_in"))
      (node (ref "C15") (pin "2") (pinfunction "2_2") (pintype "passive"))
      (node (ref "C40") (pin "1") (pinfunction "1_1") (pintype "passive"))
      (node (ref "TP_12V") (pin "1") (pinfunction "1_1") (pintype "passive"))
      (node (ref "U5") (pin "2") (pinfunction "VDD_2") (pintype "power_in"))
    )
    (net (code "4") (name "+24V") (class "Default")
      (node (ref "24V") (pin "2") (pinfunction "A_2") (pintype "passive"))
      (node (ref "A3") (pin "1") (pinfunction "IN_1") (pintype "power_in"))
      (node (ref "A4") (pin "1") (pinfunction "IN_1") (pintype "power_in"))
      (node (ref "C24") (pin "1") (pinfunction "1_1") (pintype "passive"))
      (node (ref "C8") (pin "1") (pinfunction "1_1") (pintype "passive"))
      (node (ref "TP_24V") (pin "1") (pinfunction "1_1") (pintype "passive"))
      (node (ref "XF1") (pin "3") (pinfunction "2_3") (pintype "passive"))
      (node (ref "XF1") (pin "4") (pinfunction "2_4") (pintype "passive"))
    )
    (net (code "5") (name "24VIN") (class "Default")
      (node (ref "D6") (pin "2") (pinfunction "C_2") (pintype "passive"))
      (node (ref "J2") (pin "1") (pinfunction "1_1") (pintype "passive"))
      (node (ref "J3") (pin "1") (pinfunction "+24V_1") (pintype "power_in"))
      (node (ref "XF1") (pin "1") (pinfunction "1_1") (pintype "passive"))
      (node (ref "XF1") (pin "2") (pinfunction "1_2") (pintype "passive"))
    )
    (net (code "6") (name "BOTS") (class "Default")
      (node (ref "D4") (pin "2") (pinfunction "C_2") (pintype "passive"))
      (node (ref "J2") (pin "5") (pinfunction "5_5") (pintype "passive"))
      (node (ref "R4") (pin "1") (pinfunction "1_1") (pintype "passive"))
      (node (ref "TP3") (pin "1") (pinfunction "1_1") (pintype "passive"))
    )
    (net (code "7") (name "BOTS_READ") (class "Default")
      (node (ref "A2") (pin "D16") (pinfunction "A2_D16") (pintype "bidirectional"))
      (node (ref "R12") (pin "1") (pinfunction "1_1") (pintype "passive"))
      (node (ref "R4") (pin "2") (pinfunction "2_2") (pintype "passive"))
    )
    (net (code "8") (name "BRB") (class "Default")
      (node (ref "D5") (pin "2") (pinfunction "C_2") (pintype "passive"))
      (node (ref "J2") (pin "2") (pinfunction "2_2") (pintype "passive"))
      (node (ref "R5") (pin "1") (pinfunction "1_1") (pintype "passive"))
      (node (ref "TP4") (pin "1") (pinfunction "1_1") (pintype "passive"))
    )
    (net (code "9") (name "BRB_READ") (class "Default")
      (node (ref "A2") (pin "D17") (pinfunction "A3_D17") (pintype "bidirectional"))
      (node (ref "R14") (pin "1") (pinfunction "1_1") (pintype "passive"))
      (node (ref "R5") (pin "2") (pinfunction "2_2") (pintype "passive"))
    )
    (net (code "10") (name "BTN_DIM_READ") (class "Default")
      (node (ref "A2") (pin "D18") (pinfunction "A4_D18") (pintype "bidirectional"))
      (node (ref "J4") (pin "5") (pinfunction "5_5") (pintype "passive"))
    )
    (net (code "11") (name "BTN_MC_CYCLE_READ") (class "Default")
      (node (ref "A2") (pin "D20") (pinfunction "A6_D20") (pintype "bidirectional"))
      (node (ref "J4") (pin "3") (pinfunction "3_3") (pintype "passive"))
    )
    (net (code "12") (name "BTN_MODE_READ") (class "Default")
      (node (ref "A2") (pin "D21") (pinfunction "A7_D21") (pintype "bidirectional"))
      (node (ref "J4") (pin "2") (pinfunction "2_2") (pintype "passive"))
    )
    (net (code "13") (name "BTN_PRESET_READ") (class "Default")
      (node (ref "A2") (pin "D19") (pinfunction "A5_D19") (pintype "bidirectional"))
      (node (ref "J4") (pin "4") (pinfunction "4_4") (pintype "passive"))
    )
    (net (code "14") (name "BTN_START_READ") (class "Default")
      (node (ref "A2") (pin "D22") (pinfunction "A8_D22") (pintype "bidirectional"))
      (node (ref "J4") (pin "1") (pinfunction "1_1") (pintype "passive"))
    )
    (net (code "15") (name "BUZZER_CTRL") (class "Default")
      (node (ref "A2") (pin "D3") (pinfunction "D3_D3") (pintype "bidirectional"))
      (node (ref "R11") (pin "2") (pinfunction "2_2") (pintype "passive"))
      (node (ref "U5") (pin "8") (pinfunction "EN_8") (pintype "input"))
    )
    (net (code "16") (name "CANH") (class "Default")
      (node (ref "J2") (pin "4") (pinfunction "4_4") (pintype "passive"))
      (node (ref "J3") (pin "4") (pinfunction "CANH_4") (pintype "bidirectional"))
      (node (ref "JP1") (pin "1") (pinfunction "1_1") (pintype "passive"))
      (node (ref "U27") (pin "7") (pinfunction "CANH_7") (pintype "output"))
    )
    (net (code "17") (name "CANL") (class "Default")
      (node (ref "J2") (pin "3") (pinfunction "3_3") (pintype "passive"))
      (node (ref "J3") (pin "3") (pinfunction "CANL_3") (pintype "bidirectional"))
      (node (ref "R60") (pin "2") (pinfunction "2_2") (pintype "passive"))
      (node (ref "U27") (pin "6") (pinfunction "CANL_6") (pintype "bidirectional"))
    )
    (net (code "18") (name "DIAL_AUTOCROSS") (class "Default")
      (node (ref "A2") (pin "D6") (pinfunction "D6_D6") (pintype "bidirectional"))
      (node (ref "J6") (pin "4") (pinfunction "4_4") (pintype "passive"))
    )
    (net (code "19") (name "DIAL_ENDURANCE") (class "Default")
      (node (ref "A2") (pin "D7") (pinfunction "D7_D7") (pintype "bidirectional"))
      (node (ref "J6") (pin "3") (pinfunction "3_3") (pintype "passive"))
    )
    (net (code "20") (name "DIAL_LAUNCH") (class "Default")
      (node (ref "A2") (pin "D4") (pinfunction "D4_D4") (pintype "bidirectional"))
      (node (ref "J6") (pin "6") (pinfunction "6_6") (pintype "passive"))
    )
    (net (code "21") (name "DIAL_MODE_1") (class "Default")
      (node (ref "A2") (pin "D8") (pinfunction "D8_D8") (pintype "bidirectional"))
      (node (ref "J6") (pin "2") (pinfunction "2_2") (pintype "passive"))
    )
    (net (code "22") (name "DIAL_MODE_2") (class "Default")
      (node (ref "A2") (pin "D9") (pinfunction "D9_D9") (pintype "bidirectional"))
      (node (ref "J6") (pin "1") (pinfunction "1_1") (pintype "passive"))
    )
    (net (code "23") (name "DIAL_SKIDPAD") (class "Default")
      (node (ref "A2") (pin "D5") (pinfunction "D5_D5") (pintype "bidirectional"))
      (node (ref "J6") (pin "5") (pinfunction "5_5") (pintype "passive"))
    )
    (net (code "24") (name "GND") (class "Default")
      (node (ref "A2") (pin "AGND/GND") (pinfunction "GND_AGND/GND") (pintype "power_in"))
      (node (ref "A2") (pin "GND") (pinfunction "GND_GND") (pintype "power_in"))
      (node (ref "A3") (pin "2") (pinfunction "GND_2") (pintype "power_in"))
      (node (ref "A4") (pin "2") (pinfunction "GND_2") (pintype "power_in"))
      (node (ref "C10") (pin "2") (pinfunction "2_2") (pintype "passive"))
      (node (ref "C11") (pin "2") (pinfunction "2_2") (pintype "passive"))
      (node (ref "C12") (pin "2") (pinfunction "2_2") (pintype "passive"))
      (node (ref "C15") (pin "1") (pinfunction "1_1") (pintype "passive"))
      (node (ref "C16") (pin "2") (pinfunction "2_2") (pintype "passive"))
      (node (ref "C24") (pin "2") (pinfunction "2_2") (pintype "passive"))
      (node (ref "C25") (pin "1") (pinfunction "1_1") (pintype "passive"))
      (node (ref "C33") (pin "2") (pinfunction "2_2") (pintype "passive"))
      (node (ref "C34") (pin "1") (pinfunction "1_1") (pintype "passive"))
      (node (ref "C38") (pin "1") (pinfunction "1_1") (pintype "passive"))
      (node (ref "C39") (pin "1") (pinfunction "1_1") (pintype "passive"))
      (node (ref "C40") (pin "2") (pinfunction "2_2") (pintype "passive"))
      (node (ref "C8") (pin "2") (pinfunction "2_2") (pintype "passive"))
      (node (ref "D3") (pin "1") (pinfunction "A_1") (pintype "passive"))
      (node (ref "D4") (pin "1") (pinfunction "A_1") (pintype "passive"))
      (node (ref "D5") (pin "1") (pinfunction "A_1") (pintype "passive"))
      (node (ref "D6") (pin "1") (pinfunction "A_1") (pintype "passive"))
      (node (ref "J2") (pin "8") (pinfunction "8_8") (pintype "passive"))
      (node (ref "J3") (pin "2") (pinfunction "GND_2") (pintype "power_in"))
      (node (ref "J4") (pin "6") (pinfunction "6_6") (pintype "passive"))
      (node (ref "R1") (pin "1") (pinfunction "1_1") (pintype "passive"))
      (node (ref "R10") (pin "1") (pinfunction "1_1") (pintype "passive"))
      (node (ref "R11") (pin "1") (pinfunction "1_1") (pintype "passive"))
      (node (ref "R12") (pin "2") (pinfunction "2_2") (pintype "passive"))
      (node (ref "R14") (pin "2") (pinfunction "2_2") (pintype "passive"))
      (node (ref "R2") (pin "1") (pinfunction "1_1") (pintype "passive"))
      (node (ref "R6") (pin "1") (pinfunction "1_1") (pintype "passive"))
      (node (ref "R8") (pin "2") (pinfunction "2_2") (pintype "passive"))
      (node (ref "R83") (pin "1") (pinfunction "1_1") (pintype "passive"))
      (node (ref "TP_GND") (pin "1") (pinfunction "1_1") (pintype "passive"))
      (node (ref "U1") (pin "3") (pinfunction "GND_3") (pintype "power_in"))
      (node (ref "U10") (pin "3") (pinfunction "GND_3") (pintype "power_in"))
      (node (ref "U11") (pin "3") (pinfunction "GND_3") (pintype "power_in"))
      (node (ref "U12") (pin "3") (pinfunction "GND_3") (pintype "power_in"))
      (node (ref "U13") (pin "3") (pinfunction "GND_3") (pintype "power_in"))
      (node (ref "U14") (pin "3") (pinfunction "GND_3") (pintype "power_in"))
      (node (ref "U15") (pin "3") (pinfunction "GND_3") (pintype "power_in"))
      (node (ref "U2") (pin "3") (pinfunction "GND_3") (pintype "power_in"))
      (node (ref "U27") (pin "2") (pinfunction "GND_2") (pintype "power_in"))
      (node (ref "U27") (pin "8") (pinfunction "S_8") (pintype "input"))
      (node (ref "U3") (pin "4") (pinfunction "1_4") (pintype "input"))
      (node (ref "U3") (pin "5") (pinfunction "2_5") (pintype "input"))
      (node (ref "U3") (pin "9") (pinfunction "GND_9") (pintype "power_in"))
      (node (ref "U4") (pin "3") (pinfunction "GND_3") (pintype "power_in"))
      (node (ref "U5") (pin "5") (pinfunction "GND_5") (pintype "power_in"))
      (node (ref "U6") (pin "3") (pinfunction "GND_3") (pintype "power_in"))
      (node (ref "U7") (pin "3") (pinfunction "GND_3") (pintype "power_in"))
      (node (ref "U8") (pin "3") (pinfunction "GND_3") (pintype "power_in"))
      (node (ref "U9") (pin "3") (pinfunction "GND_3") (pintype "power_in"))
    )
    (net (code "25") (name "INERTIA") (class "Default")
      (node (ref "D3") (pin "2") (pinfunction "C_2") (pintype "passive"))
      (node (ref "J2") (pin "6") (pinfunction "6_6") (pintype "passive"))
      (node (ref "R3") (pin "1") (pinfunction "1_1") (pintype "passive"))
      (node (ref "TP2") (pin "1") (pinfunction "1_1") (pintype "passive"))
    )
    (net (code "26") (name "INERTIA_READ") (class "Default")
      (node (ref "A2") (pin "D15") (pinfunction "A1_D15") (pintype "bidirectional"))
      (node (ref "R3") (pin "2") (pinfunction "2_2") (pintype "passive"))
      (node (ref "R8") (pin "1") (pinfunction "1_1") (pintype "passive"))
    )
    (net (code "27") (name "NEOPIXEL_CTRL") (class "Default")
      (node (ref "A2") (pin "D2") (pinfunction "D2_D2") (pintype "bidirectional"))
      (node (ref "U1") (pin "4") (pinfunction "DIN_4") (pintype "input"))
    )
    (net (code "28") (name "Net-(3.3V-C)") (class "Default")
      (node (ref "3.3V") (pin "1") (pinfunction "C_1") (pintype "passive"))
      (node (ref "R1") (pin "2") (pinfunction "2_2") (pintype "passive"))
    )
    (net (code "29") (name "Net-(5V-C)") (class "Default")
      (node (ref "5V") (pin "1") (pinfunction "C_1") (pintype "passive"))
      (node (ref "R10") (pin "2") (pinfunction "2_2") (pintype "passive"))
    )
    (net (code "30") (name "Net-(12V-C)") (class "Default")
      (node (ref "12V") (pin "1") (pinfunction "C_1") (pintype "passive"))
      (node (ref "R2") (pin "2") (pinfunction "2_2") (pintype "passive"))
    )
    (net (code "31") (name "Net-(24V-C)") (class "Default")
      (node (ref "24V") (pin "1") (pinfunction "C_1") (pintype "passive"))
      (node (ref "R83") (pin "2") (pinfunction "2_2") (pintype "passive"))
    )
    (net (code "32") (name "Net-(A2-(CLK)D13)") (class "Default")
      (node (ref "A2") (pin "D13") (pinfunction "(CLK)D13_D13") (pintype "bidirectional"))
      (node (ref "U3") (pin "1") (pinfunction "CLK_1") (pintype "input"))
    )
    (net (code "33") (name "Net-(A2-(CRX1)D0)") (class "Default")
      (node (ref "A2") (pin "D0") (pinfunction "(CRX1)D0_D0") (pintype "bidirectional"))
      (node (ref "U27") (pin "4") (pinfunction "RXD_4") (pintype "output"))
    )
    (net (code "34") (name "Net-(A2-(CS)D10)") (class "Default")
      (node (ref "A2") (pin "D10") (pinfunction "(CS)D10_D10") (pintype "bidirectional"))
      (node (ref "U3") (pin "7") (pinfunction "~{CS}_7") (pintype "input"))
    )
    (net (code "35") (name "Net-(A2-(CTX1)D1)") (class "Default")
      (node (ref "A2") (pin "D1") (pinfunction "(CTX1)D1_D1") (pintype "bidirectional"))
      (node (ref "U27") (pin "1") (pinfunction "TXD_1") (pintype "input"))
    )
    (net (code "36") (name "Net-(A2-(SDI)D12)") (class "Default")
      (node (ref "A2") (pin "D12") (pinfunction "(SDI)D12_D12") (pintype "bidirectional"))
      (node (ref "U3") (pin "3") (pinfunction "SDO_3") (pintype "output"))
    )
    (net (code "37") (name "Net-(A2-(SDO)D11)") (class "Default")
      (node (ref "A2") (pin "D11") (pinfunction "(SDO)D11_D11") (pintype "bidirectional"))
      (node (ref "U3") (pin "2") (pinfunction "SDI_2") (pintype "input"))
    )
    (net (code "38") (name "Net-(A2-A9)") (class "Default")
      (node (ref "A2") (pin "D23") (pinfunction "A9_D23") (pintype "bidirectional"))
      (node (ref "D1") (pin "2") (pinfunction "A_2") (pintype "passive"))
    )
    (net (code "39") (name "Net-(C25-Pad2)") (class "Default")
      (node (ref "C25") (pin "2") (pinfunction "2_2") (pintype "passive"))
      (node (ref "R36") (pin "1") (pinfunction "1_1") (pintype "passive"))
      (node (ref "R60") (pin "1") (pinfunction "1_1") (pintype "passive"))
    )
    (net (code "40") (name "Net-(D1-C)") (class "Default")
      (node (ref "D1") (pin "1") (pinfunction "C_1") (pintype "passive"))
      (node (ref "R6") (pin "2") (pinfunction "2_2") (pintype "passive"))
    )
    (net (code "41") (name "Net-(D101-A)") (class "Default")
      (node (ref "D101") (pin "7") (pinfunction "A_7") (pintype "input"))
      (node (ref "RN2") (pin "5") (pinfunction "2_5") (pintype "passive"))
    )
    (net (code "42") (name "Net-(D101-B)") (class "Default")
      (node (ref "D101") (pin "6") (pinfunction "B_6") (pintype "input"))
      (node (ref "RN2") (pin "6") (pinfunction "2_6") (pintype "passive"))
    )
    (net (code "43") (name "Net-(D101-C)") (class "Default")
      (node (ref "D101") (pin "4") (pinfunction "C_4") (pintype "input"))
      (node (ref "RN2") (pin "7") (pinfunction "2_7") (pintype "passive"))
    )
    (net (code "44") (name "Net-(D101-D)") (class "Default")
      (node (ref "D101") (pin "2") (pinfunction "D_2") (pintype "input"))
      (node (ref "RN2") (pin "8") (pinfunction "2_8") (pintype "passive"))
    )
    (net (code "45") (name "Net-(D101-E)") (class "Default")
      (node (ref "D101") (pin "1") (pinfunction "E_1") (pintype "input"))
      (node (ref "RN4") (pin "6") (pinfunction "2_6") (pintype "passive"))
    )
    (net (code "46") (name "Net-(D101-F)") (class "Default")
      (node (ref "D101") (pin "9") (pinfunction "F_9") (pintype "input"))
      (node (ref "RN4") (pin "7") (pinfunction "2_7") (pintype "passive"))
    )
    (net (code "47") (name "Net-(D101-G)") (class "Default")
      (node (ref "D101") (pin "10") (pinfunction "G_10") (pintype "input"))
      (node (ref "RN4") (pin "8") (pinfunction "2_8") (pintype "passive"))
    )
    (net (code "48") (name "Net-(JP1-Pad2)") (class "Default")
      (node (ref "JP1") (pin "2") (pinfunction "2_2") (pintype "passive"))
      (node (ref "R36") (pin "2") (pinfunction "2_2") (pintype "passive"))
    )
    (net (code "49") (name "Net-(LS100-FEEDBACK)") (class "Default")
      (node (ref "LS100") (pin "F") (pinfunction "FEEDBACK_F") (pintype "bidirectional"))
      (node (ref "R9") (pin "2") (pinfunction "2_2") (pintype "passive"))
    )
    (net (code "50") (name "Net-(LS100-GND)") (class "Default")
      (node (ref "LS100") (pin "G") (pinfunction "GND_G") (pintype "power_in"))
      (node (ref "R13") (pin "1") (pinfunction "1_1") (pintype "passive"))
      (node (ref "U5") (pin "6") (pinfunction "HORNB_6") (pintype "output"))
    )
    (net (code "51") (name "Net-(LS100-MAIN)") (class "Default")
      (node (ref "C17") (pin "1") (pinfunction "1_1") (pintype "passive"))
      (node (ref "LS100") (pin "M") (pinfunction "MAIN_M") (pintype "power_in"))
      (node (ref "U5") (pin "7") (pinfunction "HORNS_7") (pintype "output"))
    )
    (net (code "52") (name "Net-(RN2B-1)") (class "Default")
      (node (ref "RN2") (pin "2") (pinfunction "1_2") (pintype "passive"))
      (node (ref "U3") (pin "14") (pinfunction "GPA2_14") (pintype "bidirectional"))
    )
    (net (code "53") (name "Net-(RN2C-1)") (class "Default")
      (node (ref "RN2") (pin "3") (pinfunction "1_3") (pintype "passive"))
      (node (ref "U3") (pin "13") (pinfunction "GPA1_13") (pintype "bidirectional"))
    )
    (net (code "54") (name "Net-(RN2D-1)") (class "Default")
      (node (ref "RN2") (pin "4") (pinfunction "1_4") (pintype "passive"))
      (node (ref "U3") (pin "12") (pinfunction "GPA0_12") (pintype "bidirectional"))
    )
    (net (code "55") (name "Net-(RN4B-1)") (class "Default")
      (node (ref "RN4") (pin "2") (pinfunction "1_2") (pintype "passive"))
      (node (ref "U3") (pin "17") (pinfunction "GPA5_17") (pintype "bidirectional"))
    )
    (net (code "56") (name "Net-(RN4C-1)") (class "Default")
      (node (ref "RN4") (pin "3") (pinfunction "1_3") (pintype "passive"))
      (node (ref "U3") (pin "16") (pinfunction "GPA4_16") (pintype "bidirectional"))
    )
    (net (code "57") (name "Net-(U1-DOUT)") (class "Default")
      (node (ref "U1") (pin "2") (pinfunction "DOUT_2") (pintype "output"))
      (node (ref "U2") (pin "4") (pinfunction "DIN_4") (pintype "input"))
    )
    (net (code "58") (name "Net-(U2-DOUT)") (class "Default")
      (node (ref "U2") (pin "2") (pinfunction "DOUT_2") (pintype "output"))
      (node (ref "U4") (pin "4") (pinfunction "DIN_4") (pintype "input"))
    )
    (net (code "59") (name "Net-(U3-GPA3)") (class "Default")
      (node (ref "RN2") (pin "1") (pinfunction "1_1") (pintype "passive"))
      (node (ref "U3") (pin "15") (pinfunction "GPA3_15") (pintype "bidirectional"))
    )
    (net (code "60") (name "Net-(U3-GPA6)") (class "Default")
      (node (ref "RN4") (pin "1") (pinfunction "1_1") (pintype "passive"))
      (node (ref "U3") (pin "18") (pinfunction "GPA6_18") (pintype "bidirectional"))
    )
    (net (code "61") (name "Net-(U4-DOUT)") (class "Default")
      (node (ref "U4") (pin "2") (pinfunction "DOUT_2") (pintype "output"))
      (node (ref "U6") (pin "4") (pinfunction "DIN_4") (pintype "input"))
    )
    (net (code "62") (name "Net-(U5-FEED)") (class "Default")
      (node (ref "C17") (pin "2") (pinfunction "2_2") (pintype "passive"))
      (node (ref "R13") (pin "2") (pinfunction "2_2") (pintype "passive"))
      (node (ref "R9") (pin "1") (pinfunction "1_1") (pintype "passive"))
      (node (ref "U5") (pin "4") (pinfunction "FEED_4") (pintype "input"))
    )
    (net (code "63") (name "Net-(U6-DOUT)") (class "Default")
      (node (ref "U6") (pin "2") (pinfunction "DOUT_2") (pintype "output"))
      (node (ref "U7") (pin "4") (pinfunction "DIN_4") (pintype "input"))
    )
    (net (code "64") (name "Net-(U7-DOUT)") (class "Default")
      (node (ref "U7") (pin "2") (pinfunction "DOUT_2") (pintype "output"))
      (node (ref "U8") (pin "4") (pinfunction "DIN_4") (pintype "input"))
    )
    (net (code "65") (name "Net-(U8-DOUT)") (class "Default")
      (node (ref "U8") (pin "2") (pinfunction "DOUT_2") (pintype "output"))
      (node (ref "U9") (pin "4") (pinfunction "DIN_4") (pintype "input"))
    )
    (net (code "66") (name "Net-(U10-DIN)") (class "Default")
      (node (ref "U10") (pin "4") (pinfunction "DIN_4") (pintype "input"))
      (node (ref "U9") (pin "2") (pinfunction "DOUT_2") (pintype "output"))
    )
    (net (code "67") (name "Net-(U10-DOUT)") (class "Default")
      (node (ref "U10") (pin "2") (pinfunction "DOUT_2") (pintype "output"))
      (node (ref "U11") (pin "4") (pinfunction "DIN_4") (pintype "input"))
    )
    (net (code "68") (name "Net-(U11-DOUT)") (class "Default")
      (node (ref "U11") (pin "2") (pinfunction "DOUT_2") (pintype "output"))
      (node (ref "U12") (pin "4") (pinfunction "DIN_4") (pintype "input"))
    )
    (net (code "69") (name "Net-(U12-DOUT)") (class "Default")
      (node (ref "U12") (pin "2") (pinfunction "DOUT_2") (pintype "output"))
      (node (ref "U13") (pin "4") (pinfunction "DIN_4") (pintype "input"))
    )
    (net (code "70") (name "Net-(U13-DOUT)") (class "Default")
      (node (ref "U13") (pin "2") (pinfunction "DOUT_2") (pintype "output"))
      (node (ref "U14") (pin "4") (pinfunction "DIN_4") (pintype "input"))
    )
    (net (code "71") (name "Net-(U14-DOUT)") (class "Default")
      (node (ref "U14") (pin "2") (pinfunction "DOUT_2") (pintype "output"))
      (node (ref "U15") (pin "4") (pinfunction "DIN_4") (pintype "input"))
    )
    (net (code "72") (name "unconnected-(A2-A0-PadD14)") (class "Default")
      (node (ref "A2") (pin "D14") (pinfunction "A0_D14") (pintype "bidirectional"))
    )
    (net (code "73") (name "unconnected-(J2-Pad7)") (class "Default")
      (node (ref "J2") (pin "7") (pinfunction "7_7") (pintype "passive"))
    )
    (net (code "74") (name "unconnected-(U3-GPA7-Pad19)") (class "Default")
      (node (ref "U3") (pin "19") (pinfunction "GPA7_19") (pintype "bidirectional"))
    )
    (net (code "75") (name "unconnected-(U3-INT-Pad8)") (class "Default")
      (node (ref "U3") (pin "8") (pinfunction "INT_8") (pintype "output"))
    )
    (net (code "76") (name "unconnected-(U15-DOUT-Pad2)") (class "Default")
      (node (ref "U15") (pin "2") (pinfunction "DOUT_2") (pintype "output"))
    )
  )
)
